# Matrix_Game_Board.net
KiCad netlist of a schematic drawn in EAGLE
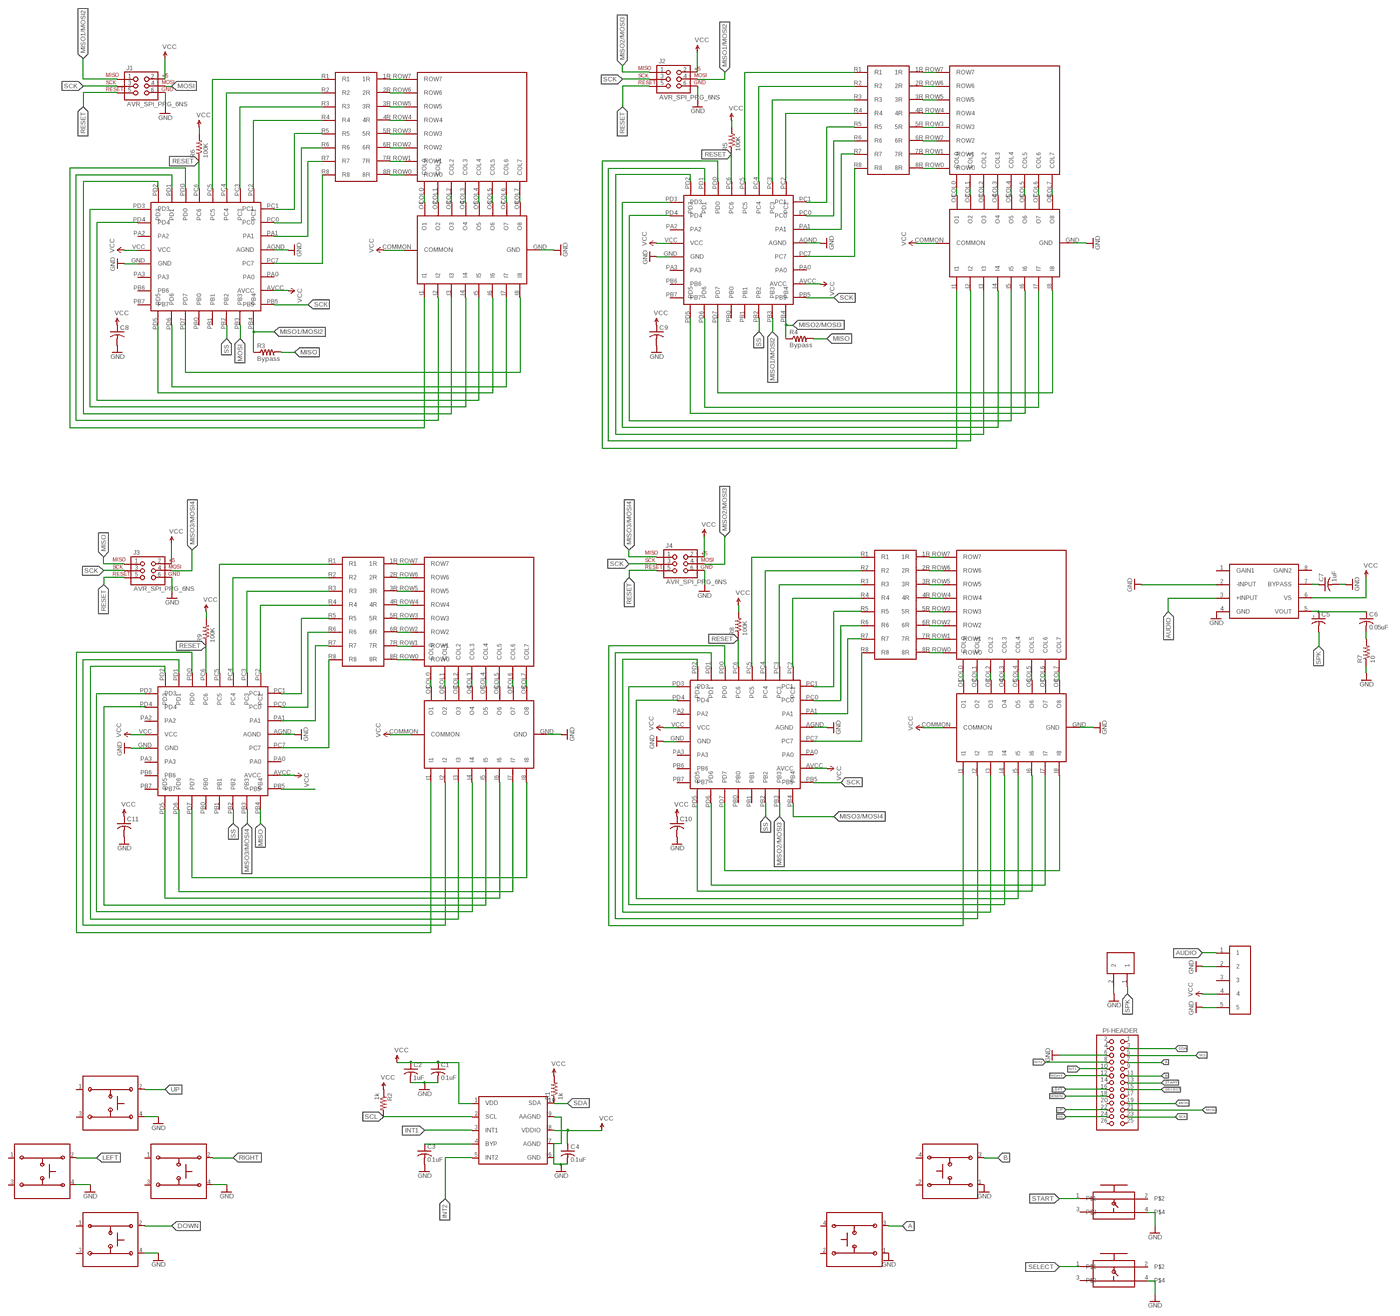
[diagram p0: schematic, sheet 1, overview]
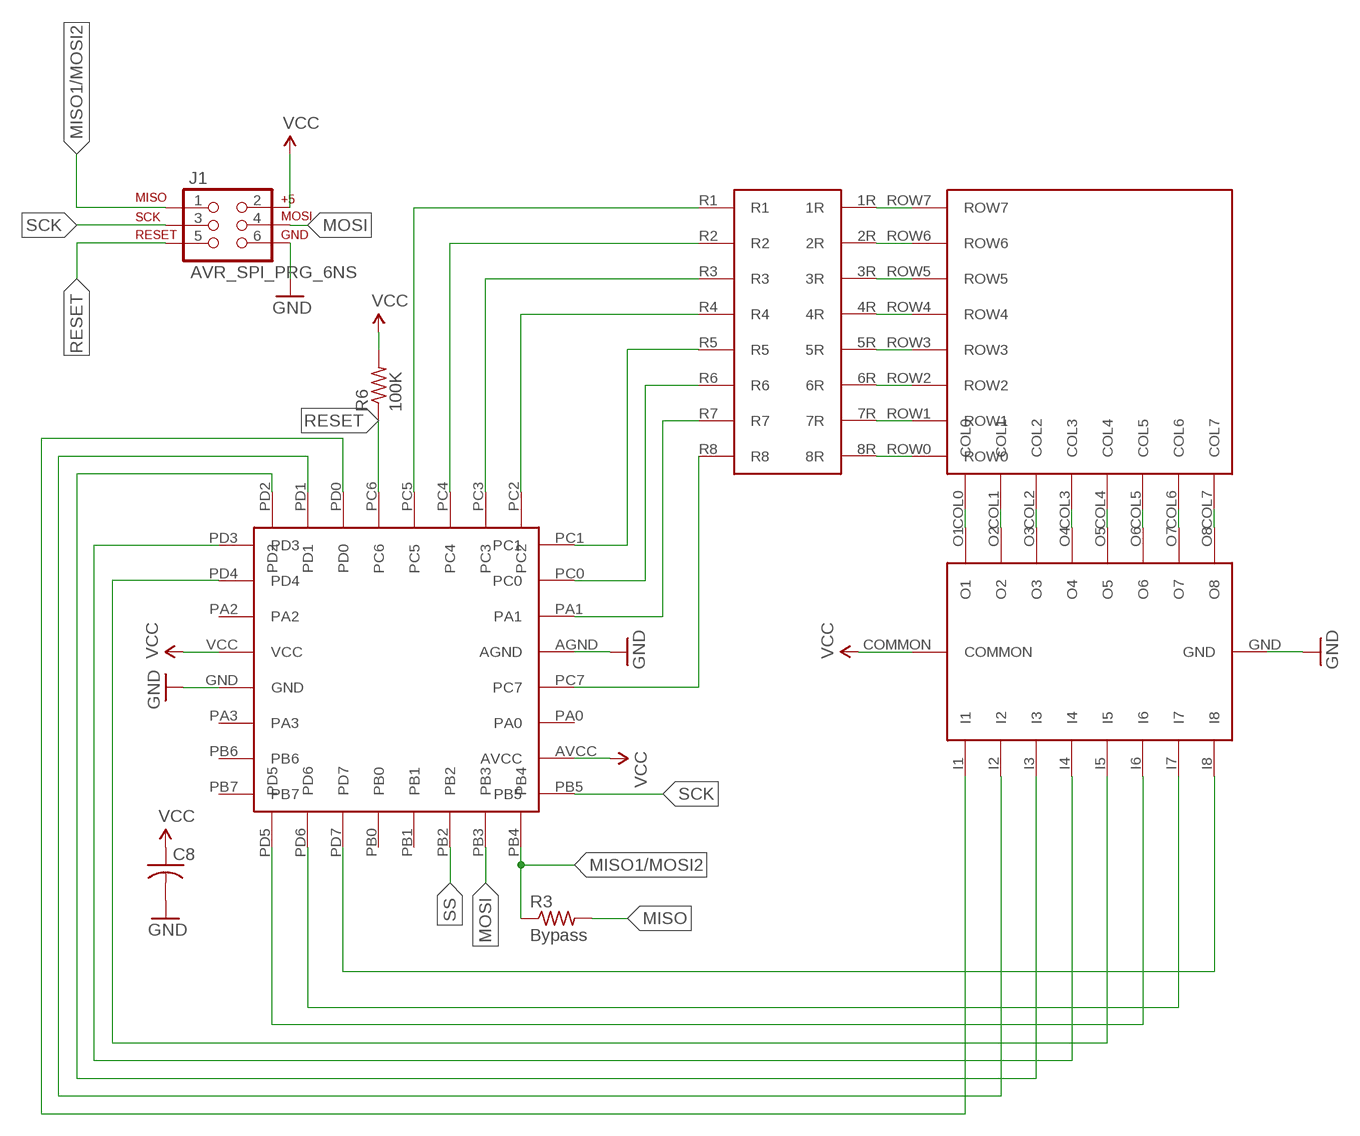
[diagram p1: schematic, sheet 1, part 1 of 4]
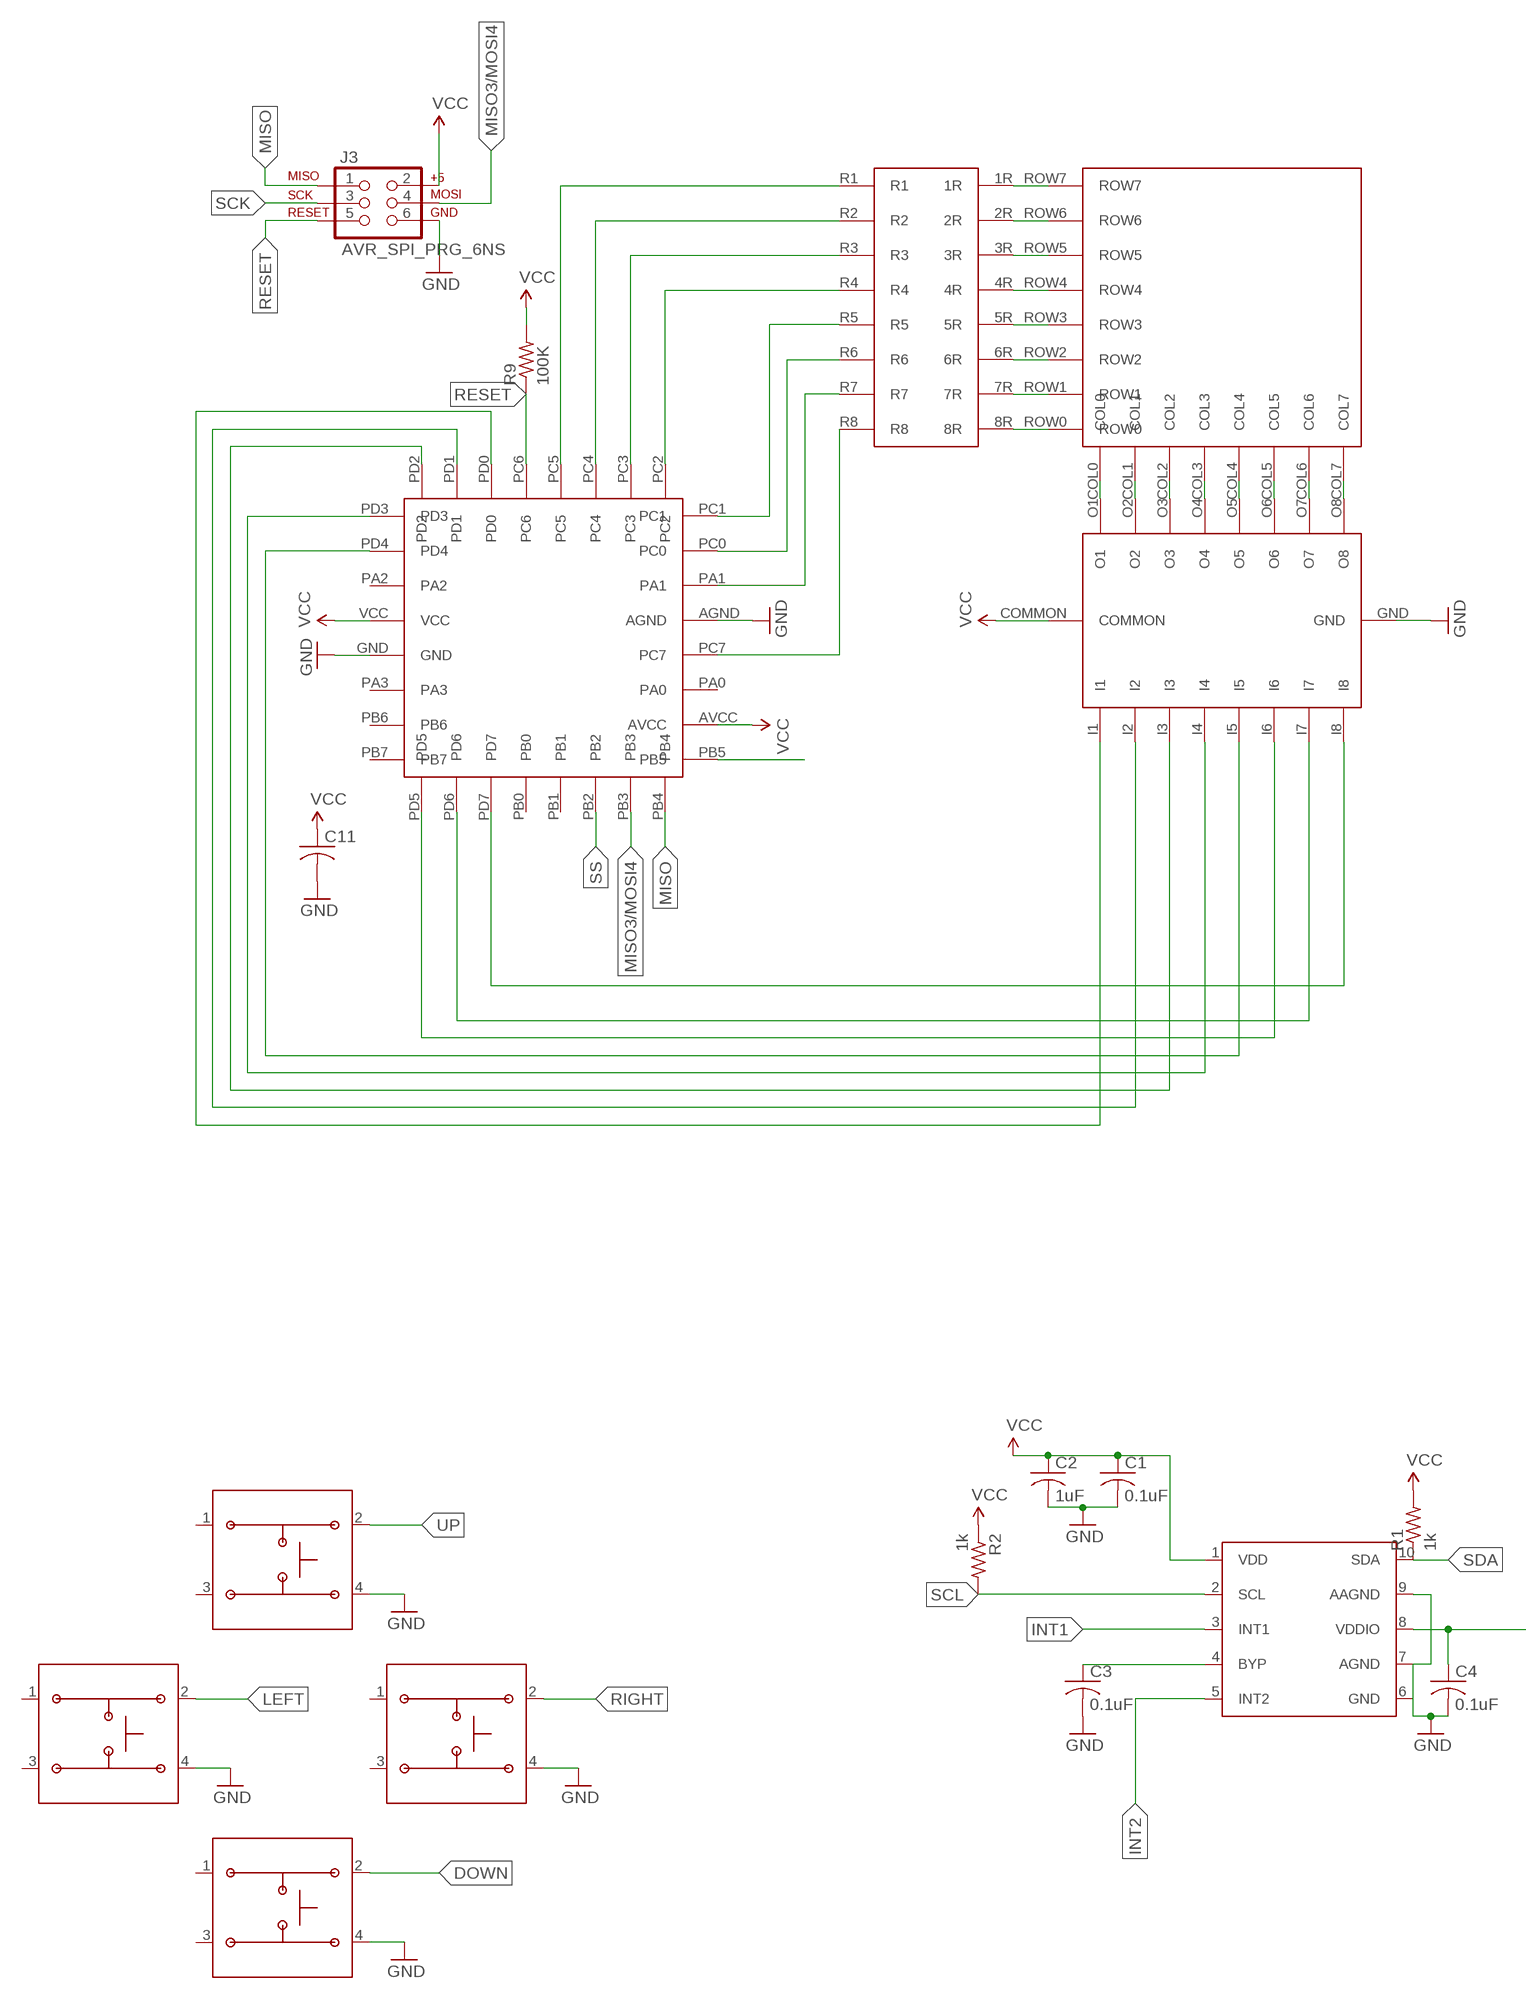
[diagram p2: schematic, sheet 1, part 2 of 4]
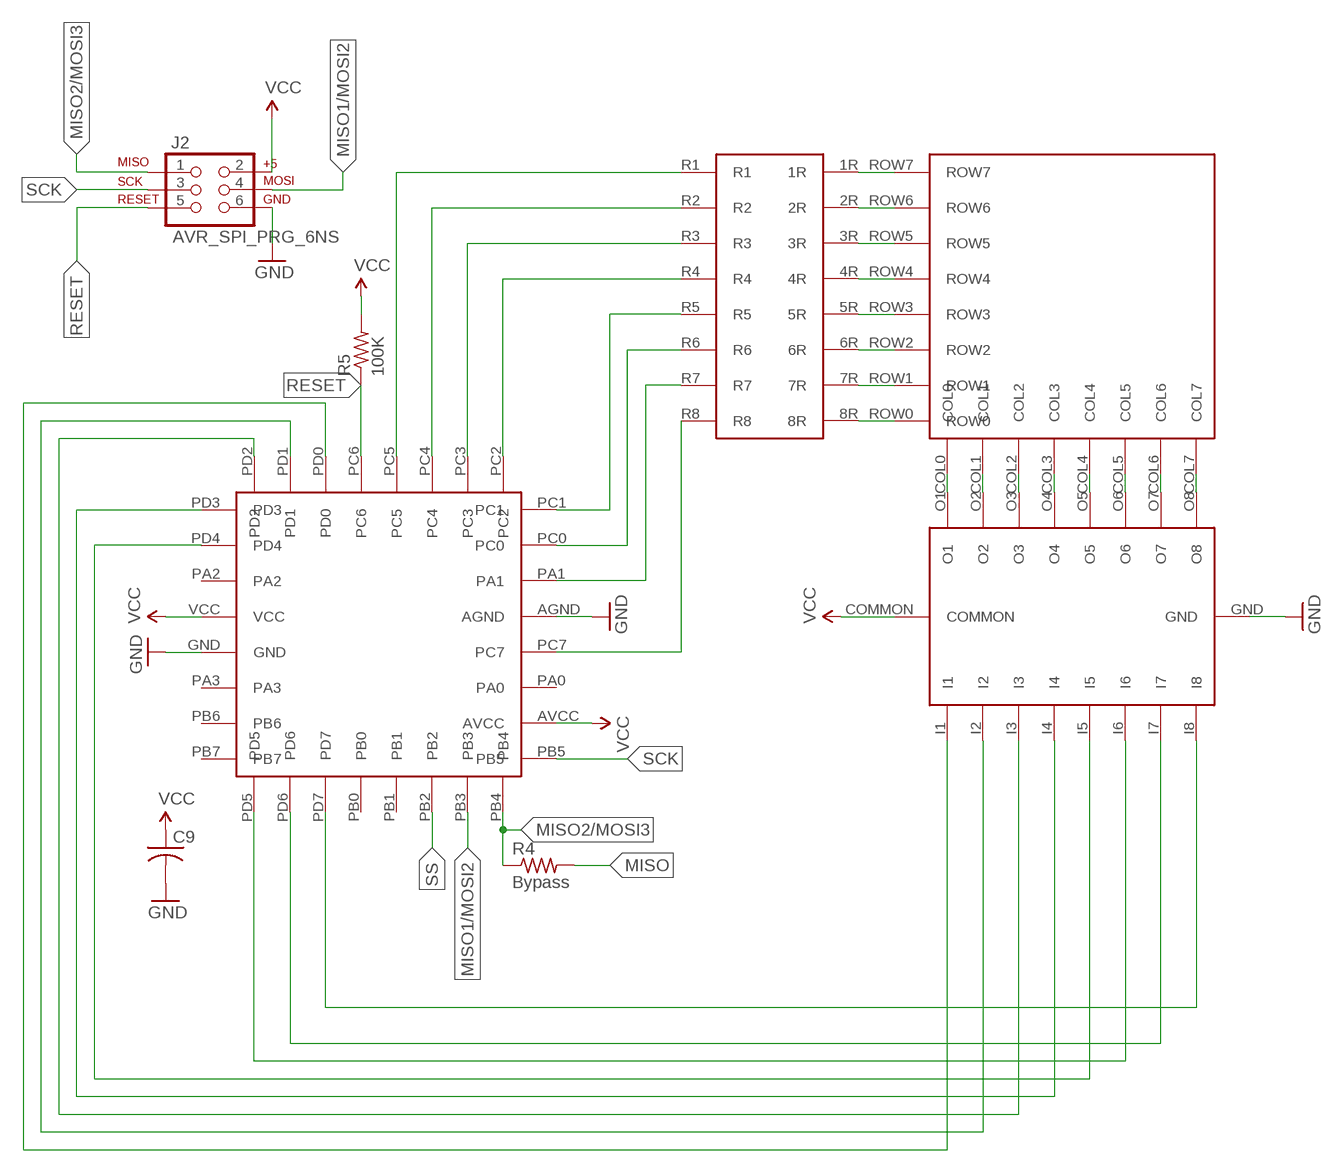
[diagram p3: schematic, sheet 1, part 3 of 4]
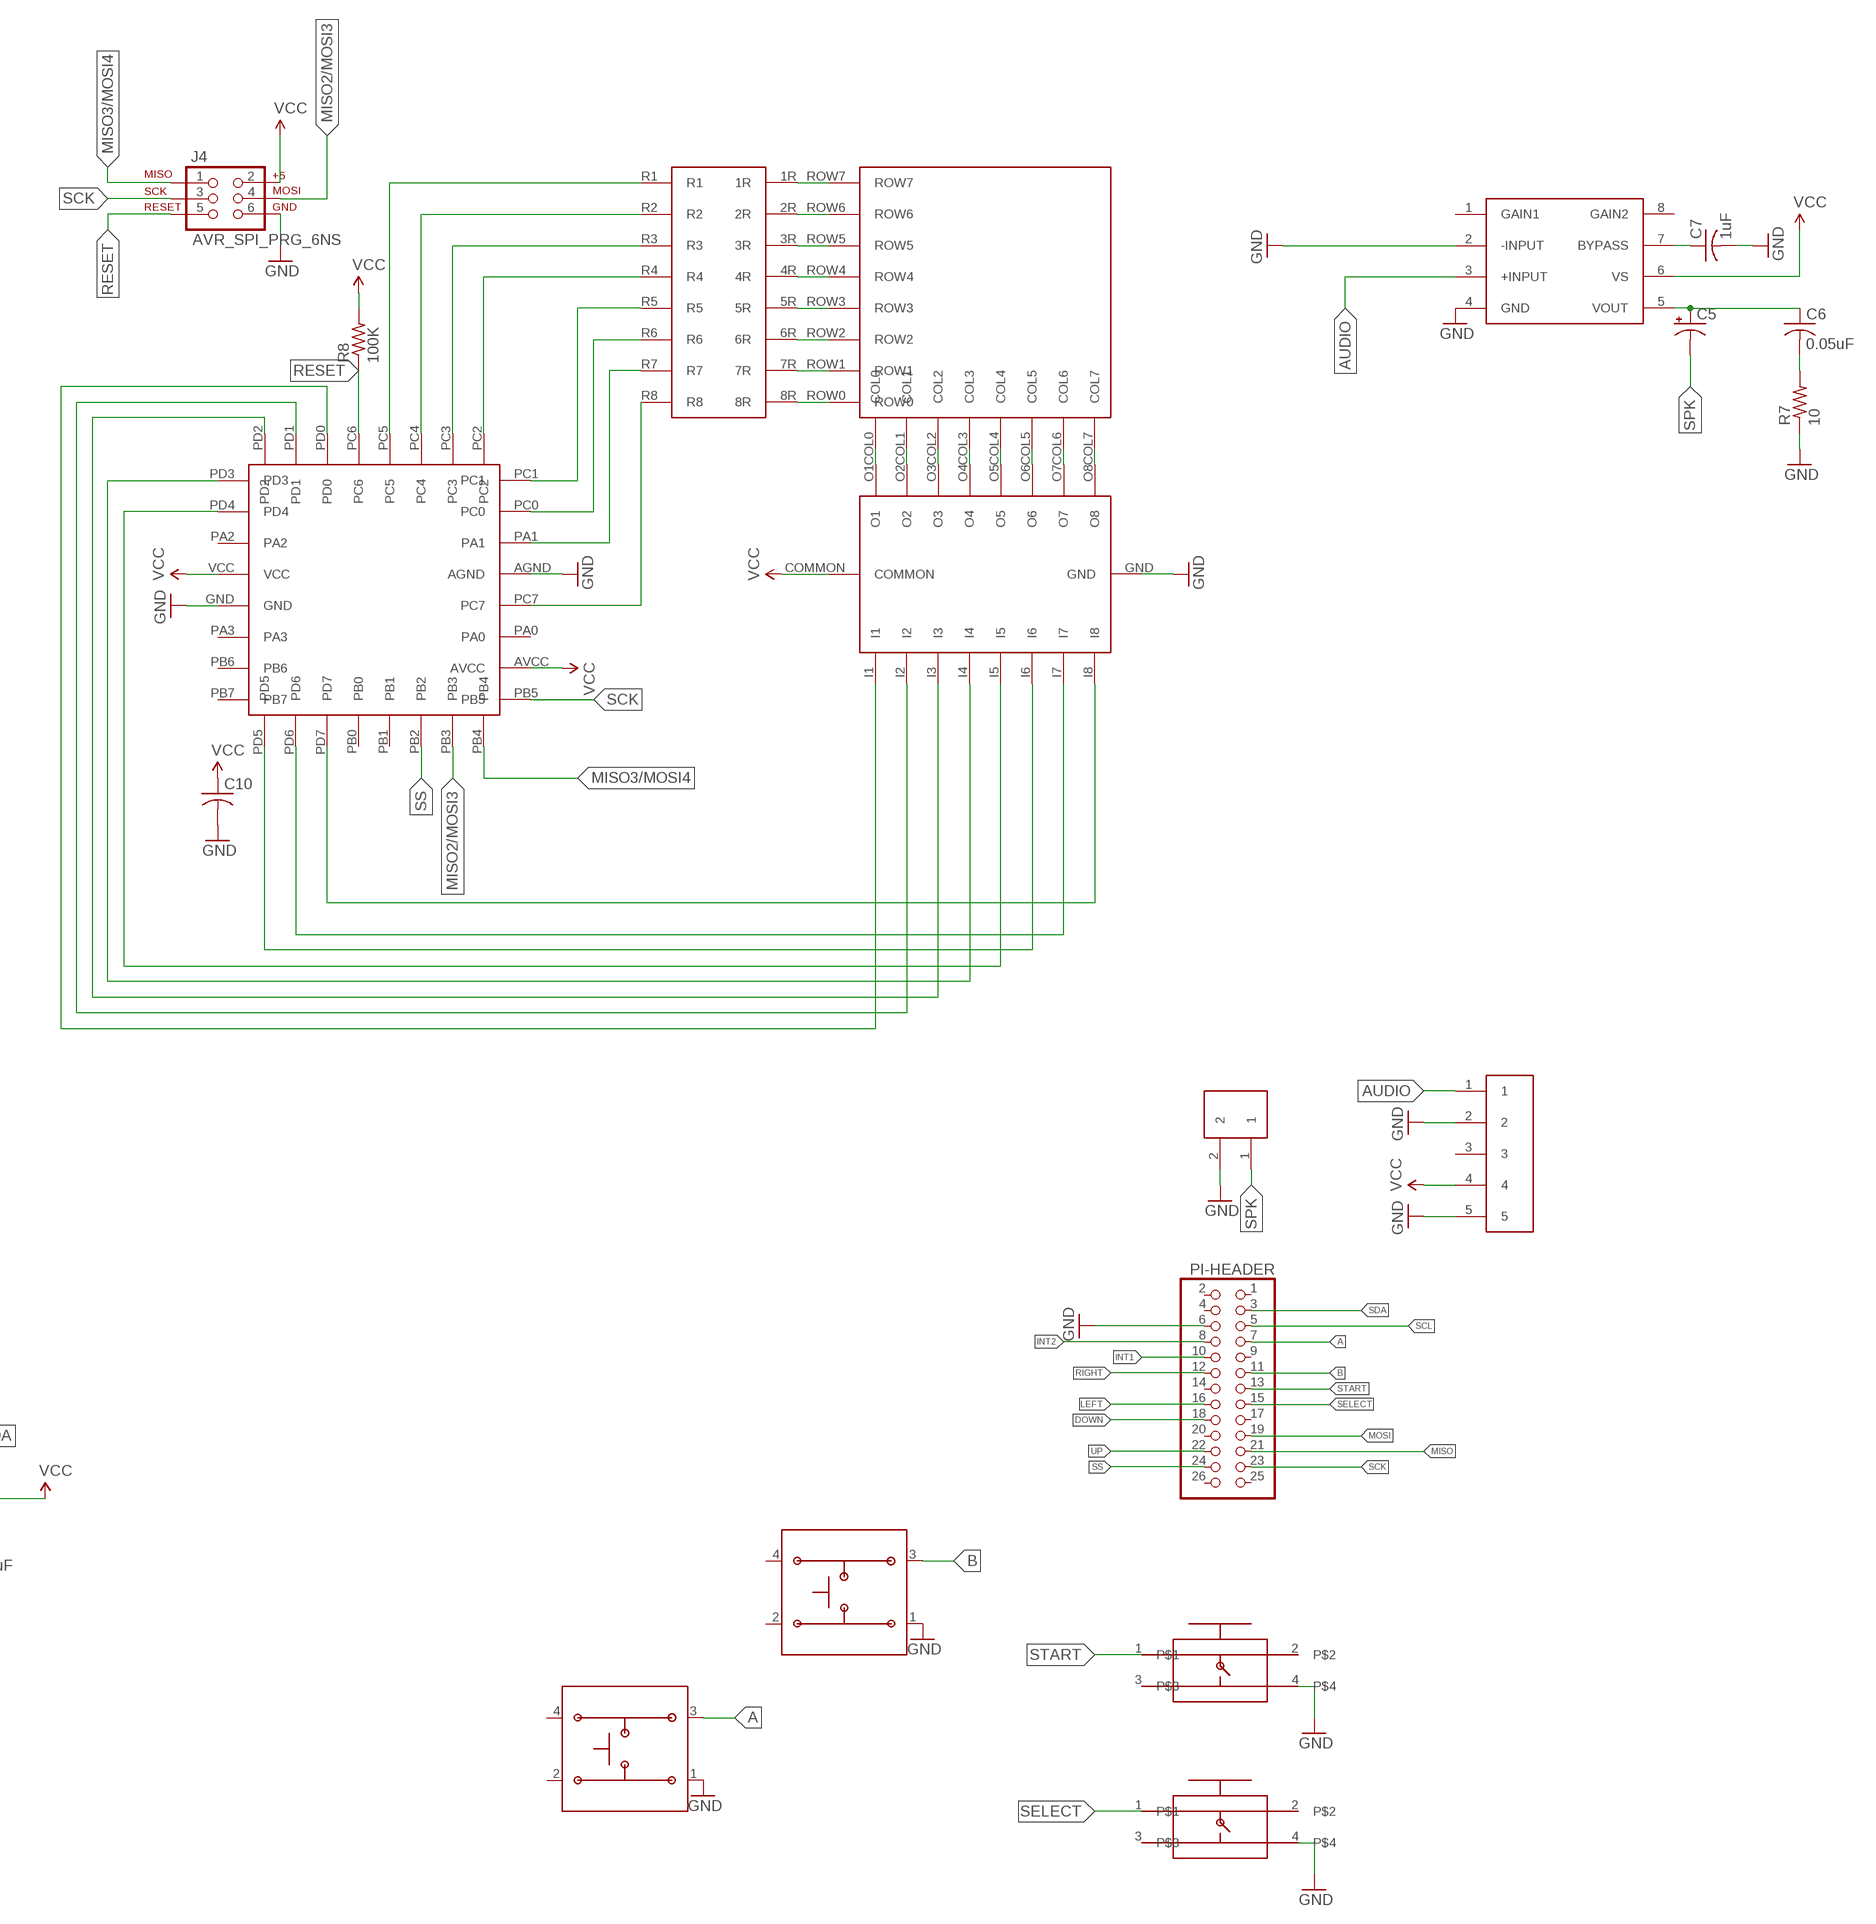
[diagram p4: schematic, sheet 1, part 4 of 4]

(export (version "E")
  (design (tool "Eeschema 10.0.6"))
  (components
    (comp (ref "C1")
      (value "0.1uF")
      (footprint "eagle-import:C0603")
      (libsource (lib "eagle-import") (part "C-USC0603"))
    )
    (comp (ref "C2")
      (value "1uF")
      (footprint "eagle-import:C0603")
      (libsource (lib "eagle-import") (part "C-USC0603"))
    )
    (comp (ref "C3")
      (value "0.1uF")
      (footprint "eagle-import:C0603")
      (libsource (lib "eagle-import") (part "C-USC0603"))
    )
    (comp (ref "C4")
      (value "0.1uF")
      (footprint "eagle-import:C0603")
      (libsource (lib "eagle-import") (part "C-USC0603"))
    )
    (comp (ref "C5")
      (value "CPOL-US153CLV-0605")
      (footprint "eagle-import:153CLV-0605")
      (libsource (lib "eagle-import") (part "CPOL-US153CLV-0605"))
    )
    (comp (ref "C6")
      (value "0.05uF")
      (footprint "eagle-import:C0603")
      (libsource (lib "eagle-import") (part "C-USC0603"))
    )
    (comp (ref "C7")
      (value "1uF")
      (footprint "eagle-import:C0603")
      (libsource (lib "eagle-import") (part "C-USC0603"))
    )
    (comp (ref "C8")
      (value "C-USC0603")
      (footprint "eagle-import:C0603")
      (libsource (lib "eagle-import") (part "C-USC0603"))
    )
    (comp (ref "C9")
      (value "C-USC0603")
      (footprint "eagle-import:C0603")
      (libsource (lib "eagle-import") (part "C-USC0603"))
    )
    (comp (ref "C10")
      (value "C-USC0603")
      (footprint "eagle-import:C0603")
      (libsource (lib "eagle-import") (part "C-USC0603"))
    )
    (comp (ref "C11")
      (value "C-USC0603")
      (footprint "eagle-import:C0603")
      (libsource (lib "eagle-import") (part "C-USC0603"))
    )
    (comp (ref "J1")
      (value "AVR_SPI_PRG_6NS")
      (footprint "eagle-import:2X3-NS")
      (libsource (lib "eagle-import") (part "AVR_SPI_PRG_6NS"))
    )
    (comp (ref "J2")
      (value "AVR_SPI_PRG_6NS")
      (footprint "eagle-import:2X3-NS")
      (libsource (lib "eagle-import") (part "AVR_SPI_PRG_6NS"))
    )
    (comp (ref "J3")
      (value "AVR_SPI_PRG_6NS")
      (footprint "eagle-import:2X3-NS")
      (libsource (lib "eagle-import") (part "AVR_SPI_PRG_6NS"))
    )
    (comp (ref "J4")
      (value "AVR_SPI_PRG_6NS")
      (footprint "eagle-import:2X3-NS")
      (libsource (lib "eagle-import") (part "AVR_SPI_PRG_6NS"))
    )
    (comp (ref "PI-HEADER")
      (value "PINHD-2X13")
      (footprint "eagle-import:2X13")
      (libsource (lib "eagle-import") (part "PINHD-2X13"))
    )
    (comp (ref "R1")
      (value "1k")
      (footprint "eagle-import:R0603")
      (libsource (lib "eagle-import") (part "R-US_R0603"))
    )
    (comp (ref "R2")
      (value "1k")
      (footprint "eagle-import:R0603")
      (libsource (lib "eagle-import") (part "R-US_R0603"))
    )
    (comp (ref "R3")
      (value "Bypass")
      (footprint "eagle-import:R0603")
      (libsource (lib "eagle-import") (part "R-US_R0603"))
    )
    (comp (ref "R4")
      (value "Bypass")
      (footprint "eagle-import:R0603")
      (libsource (lib "eagle-import") (part "R-US_R0603"))
    )
    (comp (ref "R5")
      (value "100K")
      (footprint "eagle-import:R0603")
      (libsource (lib "eagle-import") (part "R-US_R0603"))
    )
    (comp (ref "R6")
      (value "100K")
      (footprint "eagle-import:R0603")
      (libsource (lib "eagle-import") (part "R-US_R0603"))
    )
    (comp (ref "R7")
      (value "10")
      (footprint "eagle-import:R0603")
      (libsource (lib "eagle-import") (part "R-US_R0603"))
    )
    (comp (ref "R8")
      (value "100K")
      (footprint "eagle-import:R0603")
      (libsource (lib "eagle-import") (part "R-US_R0603"))
    )
    (comp (ref "R9")
      (value "100K")
      (footprint "eagle-import:R0603")
      (libsource (lib "eagle-import") (part "R-US_R0603"))
    )
    (comp (ref "U$1")
      (value "8X8_LED_MATRIX")
      (footprint "eagle-import:8X8_LED_MATRIX")
      (libsource (lib "eagle-import") (part "8X8_LED_MATRIX"))
    )
    (comp (ref "U$2")
      (value "RES_ARRAY")
      (footprint "eagle-import:RES_ARRAY")
      (libsource (lib "eagle-import") (part "RES_ARRAY"))
    )
    (comp (ref "U$3")
      (value "8X8_LED_MATRIX")
      (footprint "eagle-import:8X8_LED_MATRIX")
      (libsource (lib "eagle-import") (part "8X8_LED_MATRIX"))
    )
    (comp (ref "U$4")
      (value "ULN2803AFWG")
      (footprint "eagle-import:ULN2803AFWG")
      (libsource (lib "eagle-import") (part "ULN2803AFWG"))
    )
    (comp (ref "U$5")
      (value "ULN2803AFWG")
      (footprint "eagle-import:ULN2803AFWG")
      (libsource (lib "eagle-import") (part "ULN2803AFWG"))
    )
    (comp (ref "U$6")
      (value "ATTINY48")
      (footprint "eagle-import:ATTINY48")
      (libsource (lib "eagle-import") (part "ATTINY48"))
    )
    (comp (ref "U$7")
      (value "RES_ARRAY")
      (footprint "eagle-import:RES_ARRAY")
      (libsource (lib "eagle-import") (part "RES_ARRAY"))
    )
    (comp (ref "U$8")
      (value "8X8_LED_MATRIX")
      (footprint "eagle-import:8X8_LED_MATRIX")
      (libsource (lib "eagle-import") (part "8X8_LED_MATRIX"))
    )
    (comp (ref "U$9")
      (value "ATTINY48")
      (footprint "eagle-import:ATTINY48")
      (libsource (lib "eagle-import") (part "ATTINY48"))
    )
    (comp (ref "U$10")
      (value "ULN2803AFWG")
      (footprint "eagle-import:ULN2803AFWG")
      (libsource (lib "eagle-import") (part "ULN2803AFWG"))
    )
    (comp (ref "U$11")
      (value "ATTINY48")
      (footprint "eagle-import:ATTINY48")
      (libsource (lib "eagle-import") (part "ATTINY48"))
    )
    (comp (ref "U$12")
      (value "RES_ARRAY")
      (footprint "eagle-import:RES_ARRAY")
      (libsource (lib "eagle-import") (part "RES_ARRAY"))
    )
    (comp (ref "U$13")
      (value "8X8_LED_MATRIX")
      (footprint "eagle-import:8X8_LED_MATRIX")
      (libsource (lib "eagle-import") (part "8X8_LED_MATRIX"))
    )
    (comp (ref "U$14")
      (value "ULN2803AFWG")
      (footprint "eagle-import:ULN2803AFWG")
      (libsource (lib "eagle-import") (part "ULN2803AFWG"))
    )
    (comp (ref "U$15")
      (value "ATTINY48")
      (footprint "eagle-import:ATTINY48")
      (libsource (lib "eagle-import") (part "ATTINY48"))
    )
    (comp (ref "U$16")
      (value "RES_ARRAY")
      (footprint "eagle-import:RES_ARRAY")
      (libsource (lib "eagle-import") (part "RES_ARRAY"))
    )
    (comp (ref "U$17")
      (value "12X12MM_BUTTON")
      (footprint "eagle-import:12X12MM_BUTTON")
      (libsource (lib "eagle-import") (part "12X12MM_BUTTON"))
    )
    (comp (ref "U$18")
      (value "12X12MM_BUTTON")
      (footprint "eagle-import:12X12MM_BUTTON")
      (libsource (lib "eagle-import") (part "12X12MM_BUTTON"))
    )
    (comp (ref "U$19")
      (value "12X12MM_BUTTON")
      (footprint "eagle-import:12X12MM_BUTTON")
      (libsource (lib "eagle-import") (part "12X12MM_BUTTON"))
    )
    (comp (ref "U$20")
      (value "12X12MM_BUTTON")
      (footprint "eagle-import:12X12MM_BUTTON")
      (libsource (lib "eagle-import") (part "12X12MM_BUTTON"))
    )
    (comp (ref "U$21")
      (value "12X12MM_BUTTON")
      (footprint "eagle-import:12X12MM_BUTTON")
      (libsource (lib "eagle-import") (part "12X12MM_BUTTON"))
    )
    (comp (ref "U$22")
      (value "12X12MM_BUTTON")
      (footprint "eagle-import:12X12MM_BUTTON")
      (libsource (lib "eagle-import") (part "12X12MM_BUTTON"))
    )
    (comp (ref "U$23")
      (value "MMA8653FCR1")
      (footprint "eagle-import:MMA8653FCR1")
      (libsource (lib "eagle-import") (part "MMA8653FCR1"))
    )
    (comp (ref "U$24")
      (value "SMDTACTILE")
      (footprint "eagle-import:SMDTACTILE")
      (libsource (lib "eagle-import") (part "SMDTACTILE"))
    )
    (comp (ref "U$25")
      (value "LM386")
      (footprint "eagle-import:LM386")
      (libsource (lib "eagle-import") (part "LM386"))
    )
    (comp (ref "U$26")
      (value "SMDTACTILE")
      (footprint "eagle-import:SMDTACTILE")
      (libsource (lib "eagle-import") (part "SMDTACTILE"))
    )
    (comp (ref "U$29")
      (value "DF3_1X2")
      (footprint "eagle-import:DF3_1X2")
      (libsource (lib "eagle-import") (part "DF3_1X2"))
    )
    (comp (ref "U$30")
      (value "DF3_1X5")
      (footprint "eagle-import:DF3_1X5")
      (libsource (lib "eagle-import") (part "DF3_1X5"))
    )
  )
  (nets
    (net (code "1") (name "A") (class "Default")
      (node (ref "PI-HEADER") (pin "7") (pinfunction "7_7") (pintype "passive"))
      (node (ref "U$22") (pin "3") (pinfunction "3_3") (pintype "bidirectional"))
    )
    (net (code "2") (name "AUDIO") (class "Default")
      (node (ref "U$25") (pin "3") (pinfunction "+INPUT_3") (pintype "bidirectional"))
      (node (ref "U$30") (pin "1") (pinfunction "1_1") (pintype "bidirectional"))
    )
    (net (code "3") (name "B") (class "Default")
      (node (ref "PI-HEADER") (pin "11") (pinfunction "11_11") (pintype "passive"))
      (node (ref "U$21") (pin "3") (pinfunction "3_3") (pintype "bidirectional"))
    )
    (net (code "4") (name "DOWN") (class "Default")
      (node (ref "PI-HEADER") (pin "18") (pinfunction "18_18") (pintype "passive"))
      (node (ref "U$20") (pin "2") (pinfunction "2_2") (pintype "bidirectional"))
    )
    (net (code "5") (name "GND") (class "Default")
      (node (ref "C1") (pin "2") (pinfunction "2_2") (pintype "passive"))
      (node (ref "C10") (pin "2") (pinfunction "2_2") (pintype "passive"))
      (node (ref "C11") (pin "2") (pinfunction "2_2") (pintype "passive"))
      (node (ref "C2") (pin "2") (pinfunction "2_2") (pintype "passive"))
      (node (ref "C3") (pin "2") (pinfunction "2_2") (pintype "passive"))
      (node (ref "C4") (pin "2") (pinfunction "2_2") (pintype "passive"))
      (node (ref "C7") (pin "2") (pinfunction "2_2") (pintype "passive"))
      (node (ref "C8") (pin "2") (pinfunction "2_2") (pintype "passive"))
      (node (ref "C9") (pin "2") (pinfunction "2_2") (pintype "passive"))
      (node (ref "J1") (pin "6") (pinfunction "6_6") (pintype "passive"))
      (node (ref "J2") (pin "6") (pinfunction "6_6") (pintype "passive"))
      (node (ref "J3") (pin "6") (pinfunction "6_6") (pintype "passive"))
      (node (ref "J4") (pin "6") (pinfunction "6_6") (pintype "passive"))
      (node (ref "PI-HEADER") (pin "6") (pinfunction "6_6") (pintype "passive"))
      (node (ref "R7") (pin "1") (pinfunction "1_1") (pintype "passive"))
      (node (ref "U$10") (pin "GND") (pinfunction "GND_GND") (pintype "bidirectional"))
      (node (ref "U$11") (pin "AGND") (pinfunction "AGND_AGND") (pintype "bidirectional"))
      (node (ref "U$11") (pin "GND") (pinfunction "GND_GND") (pintype "bidirectional"))
      (node (ref "U$14") (pin "GND") (pinfunction "GND_GND") (pintype "bidirectional"))
      (node (ref "U$15") (pin "AGND") (pinfunction "AGND_AGND") (pintype "bidirectional"))
      (node (ref "U$15") (pin "GND") (pinfunction "GND_GND") (pintype "bidirectional"))
      (node (ref "U$17") (pin "4") (pinfunction "4_4") (pintype "bidirectional"))
      (node (ref "U$18") (pin "4") (pinfunction "4_4") (pintype "bidirectional"))
      (node (ref "U$19") (pin "4") (pinfunction "4_4") (pintype "bidirectional"))
      (node (ref "U$20") (pin "4") (pinfunction "4_4") (pintype "bidirectional"))
      (node (ref "U$21") (pin "1") (pinfunction "1_1") (pintype "bidirectional"))
      (node (ref "U$22") (pin "1") (pinfunction "1_1") (pintype "bidirectional"))
      (node (ref "U$23") (pin "6") (pinfunction "GND_6") (pintype "bidirectional"))
      (node (ref "U$23") (pin "7") (pinfunction "AGND_7") (pintype "bidirectional"))
      (node (ref "U$23") (pin "9") (pinfunction "AAGND_9") (pintype "bidirectional"))
      (node (ref "U$24") (pin "4") (pinfunction "P$4_4") (pintype "bidirectional"))
      (node (ref "U$25") (pin "2") (pinfunction "-INPUT_2") (pintype "bidirectional"))
      (node (ref "U$25") (pin "4") (pinfunction "GND_4") (pintype "bidirectional"))
      (node (ref "U$26") (pin "4") (pinfunction "P$4_4") (pintype "bidirectional"))
      (node (ref "U$29") (pin "2") (pinfunction "2_2") (pintype "bidirectional"))
      (node (ref "U$30") (pin "2") (pinfunction "2_2") (pintype "bidirectional"))
      (node (ref "U$30") (pin "5") (pinfunction "5_5") (pintype "bidirectional"))
      (node (ref "U$4") (pin "GND") (pinfunction "GND_GND") (pintype "bidirectional"))
      (node (ref "U$5") (pin "GND") (pinfunction "GND_GND") (pintype "bidirectional"))
      (node (ref "U$6") (pin "AGND") (pinfunction "AGND_AGND") (pintype "bidirectional"))
      (node (ref "U$6") (pin "GND") (pinfunction "GND_GND") (pintype "bidirectional"))
      (node (ref "U$9") (pin "AGND") (pinfunction "AGND_AGND") (pintype "bidirectional"))
      (node (ref "U$9") (pin "GND") (pinfunction "GND_GND") (pintype "bidirectional"))
    )
    (net (code "6") (name "INT1") (class "Default")
      (node (ref "PI-HEADER") (pin "10") (pinfunction "10_10") (pintype "passive"))
      (node (ref "U$23") (pin "3") (pinfunction "INT1_3") (pintype "bidirectional"))
    )
    (net (code "7") (name "INT2") (class "Default")
      (node (ref "PI-HEADER") (pin "8") (pinfunction "8_8") (pintype "passive"))
      (node (ref "U$23") (pin "5") (pinfunction "INT2_5") (pintype "bidirectional"))
    )
    (net (code "8") (name "LEFT") (class "Default")
      (node (ref "PI-HEADER") (pin "16") (pinfunction "16_16") (pintype "passive"))
      (node (ref "U$18") (pin "2") (pinfunction "2_2") (pintype "bidirectional"))
    )
    (net (code "9") (name "MISO") (class "Default")
      (node (ref "J3") (pin "1") (pinfunction "1_1") (pintype "passive"))
      (node (ref "PI-HEADER") (pin "21") (pinfunction "21_21") (pintype "passive"))
      (node (ref "R3") (pin "2") (pinfunction "2_2") (pintype "passive"))
      (node (ref "R4") (pin "2") (pinfunction "2_2") (pintype "passive"))
      (node (ref "U$11") (pin "PB4") (pinfunction "PB4_PB4") (pintype "bidirectional"))
    )
    (net (code "10") (name "MISO1{slash}MOSI2") (class "Default")
      (node (ref "J1") (pin "1") (pinfunction "1_1") (pintype "passive"))
      (node (ref "J2") (pin "4") (pinfunction "4_4") (pintype "passive"))
      (node (ref "R3") (pin "1") (pinfunction "1_1") (pintype "passive"))
      (node (ref "U$6") (pin "PB3") (pinfunction "PB3_PB3") (pintype "bidirectional"))
      (node (ref "U$9") (pin "PB4") (pinfunction "PB4_PB4") (pintype "bidirectional"))
    )
    (net (code "11") (name "MISO2{slash}MOSI3") (class "Default")
      (node (ref "J2") (pin "1") (pinfunction "1_1") (pintype "passive"))
      (node (ref "J4") (pin "4") (pinfunction "4_4") (pintype "passive"))
      (node (ref "R4") (pin "1") (pinfunction "1_1") (pintype "passive"))
      (node (ref "U$15") (pin "PB3") (pinfunction "PB3_PB3") (pintype "bidirectional"))
      (node (ref "U$6") (pin "PB4") (pinfunction "PB4_PB4") (pintype "bidirectional"))
    )
    (net (code "12") (name "MISO3{slash}MOSI4") (class "Default")
      (node (ref "J3") (pin "4") (pinfunction "4_4") (pintype "passive"))
      (node (ref "J4") (pin "1") (pinfunction "1_1") (pintype "passive"))
      (node (ref "U$11") (pin "PB3") (pinfunction "PB3_PB3") (pintype "bidirectional"))
      (node (ref "U$15") (pin "PB4") (pinfunction "PB4_PB4") (pintype "bidirectional"))
    )
    (net (code "13") (name "MOSI") (class "Default")
      (node (ref "J1") (pin "4") (pinfunction "4_4") (pintype "passive"))
      (node (ref "PI-HEADER") (pin "19") (pinfunction "19_19") (pintype "passive"))
      (node (ref "U$9") (pin "PB3") (pinfunction "PB3_PB3") (pintype "bidirectional"))
    )
    (net (code "14") (name "Net-(C6-Pad2)") (class "Default")
      (node (ref "C6") (pin "2") (pinfunction "2_2") (pintype "passive"))
      (node (ref "R7") (pin "2") (pinfunction "2_2") (pintype "passive"))
    )
    (net (code "15") (name "Net-(U$1-PadCOL0)") (class "Default")
      (node (ref "U$1") (pin "COL0") (pinfunction "COL0_COL0") (pintype "bidirectional"))
      (node (ref "U$5") (pin "O1") (pinfunction "O1_O1") (pintype "bidirectional"))
    )
    (net (code "16") (name "Net-(U$1-PadCOL1)") (class "Default")
      (node (ref "U$1") (pin "COL1") (pinfunction "COL1_COL1") (pintype "bidirectional"))
      (node (ref "U$5") (pin "O2") (pinfunction "O2_O2") (pintype "bidirectional"))
    )
    (net (code "17") (name "Net-(U$1-PadCOL2)") (class "Default")
      (node (ref "U$1") (pin "COL2") (pinfunction "COL2_COL2") (pintype "bidirectional"))
      (node (ref "U$5") (pin "O3") (pinfunction "O3_O3") (pintype "bidirectional"))
    )
    (net (code "18") (name "Net-(U$1-PadCOL3)") (class "Default")
      (node (ref "U$1") (pin "COL3") (pinfunction "COL3_COL3") (pintype "bidirectional"))
      (node (ref "U$5") (pin "O4") (pinfunction "O4_O4") (pintype "bidirectional"))
    )
    (net (code "19") (name "Net-(U$1-PadCOL4)") (class "Default")
      (node (ref "U$1") (pin "COL4") (pinfunction "COL4_COL4") (pintype "bidirectional"))
      (node (ref "U$5") (pin "O5") (pinfunction "O5_O5") (pintype "bidirectional"))
    )
    (net (code "20") (name "Net-(U$1-PadCOL5)") (class "Default")
      (node (ref "U$1") (pin "COL5") (pinfunction "COL5_COL5") (pintype "bidirectional"))
      (node (ref "U$5") (pin "O6") (pinfunction "O6_O6") (pintype "bidirectional"))
    )
    (net (code "21") (name "Net-(U$1-PadCOL6)") (class "Default")
      (node (ref "U$1") (pin "COL6") (pinfunction "COL6_COL6") (pintype "bidirectional"))
      (node (ref "U$5") (pin "O7") (pinfunction "O7_O7") (pintype "bidirectional"))
    )
    (net (code "22") (name "Net-(U$1-PadCOL7)") (class "Default")
      (node (ref "U$1") (pin "COL7") (pinfunction "COL7_COL7") (pintype "bidirectional"))
      (node (ref "U$5") (pin "O8") (pinfunction "O8_O8") (pintype "bidirectional"))
    )
    (net (code "23") (name "Net-(U$1-PadROW0)") (class "Default")
      (node (ref "U$1") (pin "ROW0") (pinfunction "ROW0_ROW0") (pintype "bidirectional"))
      (node (ref "U$2") (pin "8R") (pinfunction "8R_8R") (pintype "bidirectional"))
    )
    (net (code "24") (name "Net-(U$1-PadROW1)") (class "Default")
      (node (ref "U$1") (pin "ROW1") (pinfunction "ROW1_ROW1") (pintype "bidirectional"))
      (node (ref "U$2") (pin "7R") (pinfunction "7R_7R") (pintype "bidirectional"))
    )
    (net (code "25") (name "Net-(U$1-PadROW2)") (class "Default")
      (node (ref "U$1") (pin "ROW2") (pinfunction "ROW2_ROW2") (pintype "bidirectional"))
      (node (ref "U$2") (pin "6R") (pinfunction "6R_6R") (pintype "bidirectional"))
    )
    (net (code "26") (name "Net-(U$1-PadROW3)") (class "Default")
      (node (ref "U$1") (pin "ROW3") (pinfunction "ROW3_ROW3") (pintype "bidirectional"))
      (node (ref "U$2") (pin "5R") (pinfunction "5R_5R") (pintype "bidirectional"))
    )
    (net (code "27") (name "Net-(U$1-PadROW4)") (class "Default")
      (node (ref "U$1") (pin "ROW4") (pinfunction "ROW4_ROW4") (pintype "bidirectional"))
      (node (ref "U$2") (pin "4R") (pinfunction "4R_4R") (pintype "bidirectional"))
    )
    (net (code "28") (name "Net-(U$1-PadROW5)") (class "Default")
      (node (ref "U$1") (pin "ROW5") (pinfunction "ROW5_ROW5") (pintype "bidirectional"))
      (node (ref "U$2") (pin "3R") (pinfunction "3R_3R") (pintype "bidirectional"))
    )
    (net (code "29") (name "Net-(U$1-PadROW6)") (class "Default")
      (node (ref "U$1") (pin "ROW6") (pinfunction "ROW6_ROW6") (pintype "bidirectional"))
      (node (ref "U$2") (pin "2R") (pinfunction "2R_2R") (pintype "bidirectional"))
    )
    (net (code "30") (name "Net-(U$1-PadROW7)") (class "Default")
      (node (ref "U$1") (pin "ROW7") (pinfunction "ROW7_ROW7") (pintype "bidirectional"))
      (node (ref "U$2") (pin "1R") (pinfunction "1R_1R") (pintype "bidirectional"))
    )
    (net (code "31") (name "Net-(U$2-PadR1)") (class "Default")
      (node (ref "U$2") (pin "R1") (pinfunction "R1_R1") (pintype "bidirectional"))
      (node (ref "U$9") (pin "PC5") (pinfunction "PC5_PC5") (pintype "bidirectional"))
    )
    (net (code "32") (name "Net-(U$2-PadR2)") (class "Default")
      (node (ref "U$2") (pin "R2") (pinfunction "R2_R2") (pintype "bidirectional"))
      (node (ref "U$9") (pin "PC4") (pinfunction "PC4_PC4") (pintype "bidirectional"))
    )
    (net (code "33") (name "Net-(U$2-PadR3)") (class "Default")
      (node (ref "U$2") (pin "R3") (pinfunction "R3_R3") (pintype "bidirectional"))
      (node (ref "U$9") (pin "PC3") (pinfunction "PC3_PC3") (pintype "bidirectional"))
    )
    (net (code "34") (name "Net-(U$2-PadR4)") (class "Default")
      (node (ref "U$2") (pin "R4") (pinfunction "R4_R4") (pintype "bidirectional"))
      (node (ref "U$9") (pin "PC2") (pinfunction "PC2_PC2") (pintype "bidirectional"))
    )
    (net (code "35") (name "Net-(U$2-PadR5)") (class "Default")
      (node (ref "U$2") (pin "R5") (pinfunction "R5_R5") (pintype "bidirectional"))
      (node (ref "U$9") (pin "PC1") (pinfunction "PC1_PC1") (pintype "bidirectional"))
    )
    (net (code "36") (name "Net-(U$2-PadR6)") (class "Default")
      (node (ref "U$2") (pin "R6") (pinfunction "R6_R6") (pintype "bidirectional"))
      (node (ref "U$9") (pin "PC0") (pinfunction "PC0_PC0") (pintype "bidirectional"))
    )
    (net (code "37") (name "Net-(U$2-PadR7)") (class "Default")
      (node (ref "U$2") (pin "R7") (pinfunction "R7_R7") (pintype "bidirectional"))
      (node (ref "U$9") (pin "PA1") (pinfunction "PA1_PA1") (pintype "bidirectional"))
    )
    (net (code "38") (name "Net-(U$2-PadR8)") (class "Default")
      (node (ref "U$2") (pin "R8") (pinfunction "R8_R8") (pintype "bidirectional"))
      (node (ref "U$9") (pin "PC7") (pinfunction "PC7_PC7") (pintype "bidirectional"))
    )
    (net (code "39") (name "Net-(U$3-PadCOL0)") (class "Default")
      (node (ref "U$3") (pin "COL0") (pinfunction "COL0_COL0") (pintype "bidirectional"))
      (node (ref "U$4") (pin "O1") (pinfunction "O1_O1") (pintype "bidirectional"))
    )
    (net (code "40") (name "Net-(U$3-PadCOL1)") (class "Default")
      (node (ref "U$3") (pin "COL1") (pinfunction "COL1_COL1") (pintype "bidirectional"))
      (node (ref "U$4") (pin "O2") (pinfunction "O2_O2") (pintype "bidirectional"))
    )
    (net (code "41") (name "Net-(U$3-PadCOL2)") (class "Default")
      (node (ref "U$3") (pin "COL2") (pinfunction "COL2_COL2") (pintype "bidirectional"))
      (node (ref "U$4") (pin "O3") (pinfunction "O3_O3") (pintype "bidirectional"))
    )
    (net (code "42") (name "Net-(U$3-PadCOL3)") (class "Default")
      (node (ref "U$3") (pin "COL3") (pinfunction "COL3_COL3") (pintype "bidirectional"))
      (node (ref "U$4") (pin "O4") (pinfunction "O4_O4") (pintype "bidirectional"))
    )
    (net (code "43") (name "Net-(U$3-PadCOL4)") (class "Default")
      (node (ref "U$3") (pin "COL4") (pinfunction "COL4_COL4") (pintype "bidirectional"))
      (node (ref "U$4") (pin "O5") (pinfunction "O5_O5") (pintype "bidirectional"))
    )
    (net (code "44") (name "Net-(U$3-PadCOL5)") (class "Default")
      (node (ref "U$3") (pin "COL5") (pinfunction "COL5_COL5") (pintype "bidirectional"))
      (node (ref "U$4") (pin "O6") (pinfunction "O6_O6") (pintype "bidirectional"))
    )
    (net (code "45") (name "Net-(U$3-PadCOL6)") (class "Default")
      (node (ref "U$3") (pin "COL6") (pinfunction "COL6_COL6") (pintype "bidirectional"))
      (node (ref "U$4") (pin "O7") (pinfunction "O7_O7") (pintype "bidirectional"))
    )
    (net (code "46") (name "Net-(U$3-PadCOL7)") (class "Default")
      (node (ref "U$3") (pin "COL7") (pinfunction "COL7_COL7") (pintype "bidirectional"))
      (node (ref "U$4") (pin "O8") (pinfunction "O8_O8") (pintype "bidirectional"))
    )
    (net (code "47") (name "Net-(U$3-PadROW0)") (class "Default")
      (node (ref "U$3") (pin "ROW0") (pinfunction "ROW0_ROW0") (pintype "bidirectional"))
      (node (ref "U$7") (pin "8R") (pinfunction "8R_8R") (pintype "bidirectional"))
    )
    (net (code "48") (name "Net-(U$3-PadROW1)") (class "Default")
      (node (ref "U$3") (pin "ROW1") (pinfunction "ROW1_ROW1") (pintype "bidirectional"))
      (node (ref "U$7") (pin "7R") (pinfunction "7R_7R") (pintype "bidirectional"))
    )
    (net (code "49") (name "Net-(U$3-PadROW2)") (class "Default")
      (node (ref "U$3") (pin "ROW2") (pinfunction "ROW2_ROW2") (pintype "bidirectional"))
      (node (ref "U$7") (pin "6R") (pinfunction "6R_6R") (pintype "bidirectional"))
    )
    (net (code "50") (name "Net-(U$3-PadROW3)") (class "Default")
      (node (ref "U$3") (pin "ROW3") (pinfunction "ROW3_ROW3") (pintype "bidirectional"))
      (node (ref "U$7") (pin "5R") (pinfunction "5R_5R") (pintype "bidirectional"))
    )
    (net (code "51") (name "Net-(U$3-PadROW4)") (class "Default")
      (node (ref "U$3") (pin "ROW4") (pinfunction "ROW4_ROW4") (pintype "bidirectional"))
      (node (ref "U$7") (pin "4R") (pinfunction "4R_4R") (pintype "bidirectional"))
    )
    (net (code "52") (name "Net-(U$3-PadROW5)") (class "Default")
      (node (ref "U$3") (pin "ROW5") (pinfunction "ROW5_ROW5") (pintype "bidirectional"))
      (node (ref "U$7") (pin "3R") (pinfunction "3R_3R") (pintype "bidirectional"))
    )
    (net (code "53") (name "Net-(U$3-PadROW6)") (class "Default")
      (node (ref "U$3") (pin "ROW6") (pinfunction "ROW6_ROW6") (pintype "bidirectional"))
      (node (ref "U$7") (pin "2R") (pinfunction "2R_2R") (pintype "bidirectional"))
    )
    (net (code "54") (name "Net-(U$3-PadROW7)") (class "Default")
      (node (ref "U$3") (pin "ROW7") (pinfunction "ROW7_ROW7") (pintype "bidirectional"))
      (node (ref "U$7") (pin "1R") (pinfunction "1R_1R") (pintype "bidirectional"))
    )
    (net (code "55") (name "Net-(U$4-PadI1)") (class "Default")
      (node (ref "U$4") (pin "I1") (pinfunction "I1_I1") (pintype "bidirectional"))
      (node (ref "U$6") (pin "PD0") (pinfunction "PD0_PD0") (pintype "bidirectional"))
    )
    (net (code "56") (name "Net-(U$4-PadI2)") (class "Default")
      (node (ref "U$4") (pin "I2") (pinfunction "I2_I2") (pintype "bidirectional"))
      (node (ref "U$6") (pin "PD1") (pinfunction "PD1_PD1") (pintype "bidirectional"))
    )
    (net (code "57") (name "Net-(U$4-PadI3)") (class "Default")
      (node (ref "U$4") (pin "I3") (pinfunction "I3_I3") (pintype "bidirectional"))
      (node (ref "U$6") (pin "PD2") (pinfunction "PD2_PD2") (pintype "bidirectional"))
    )
    (net (code "58") (name "Net-(U$4-PadI4)") (class "Default")
      (node (ref "U$4") (pin "I4") (pinfunction "I4_I4") (pintype "bidirectional"))
      (node (ref "U$6") (pin "PD3") (pinfunction "PD3_PD3") (pintype "bidirectional"))
    )
    (net (code "59") (name "Net-(U$4-PadI5)") (class "Default")
      (node (ref "U$4") (pin "I5") (pinfunction "I5_I5") (pintype "bidirectional"))
      (node (ref "U$6") (pin "PD4") (pinfunction "PD4_PD4") (pintype "bidirectional"))
    )
    (net (code "60") (name "Net-(U$4-PadI6)") (class "Default")
      (node (ref "U$4") (pin "I6") (pinfunction "I6_I6") (pintype "bidirectional"))
      (node (ref "U$6") (pin "PD5") (pinfunction "PD5_PD5") (pintype "bidirectional"))
    )
    (net (code "61") (name "Net-(U$4-PadI7)") (class "Default")
      (node (ref "U$4") (pin "I7") (pinfunction "I7_I7") (pintype "bidirectional"))
      (node (ref "U$6") (pin "PD6") (pinfunction "PD6_PD6") (pintype "bidirectional"))
    )
    (net (code "62") (name "Net-(U$4-PadI8)") (class "Default")
      (node (ref "U$4") (pin "I8") (pinfunction "I8_I8") (pintype "bidirectional"))
      (node (ref "U$6") (pin "PD7") (pinfunction "PD7_PD7") (pintype "bidirectional"))
    )
    (net (code "63") (name "Net-(U$5-PadI1)") (class "Default")
      (node (ref "U$5") (pin "I1") (pinfunction "I1_I1") (pintype "bidirectional"))
      (node (ref "U$9") (pin "PD0") (pinfunction "PD0_PD0") (pintype "bidirectional"))
    )
    (net (code "64") (name "Net-(U$5-PadI2)") (class "Default")
      (node (ref "U$5") (pin "I2") (pinfunction "I2_I2") (pintype "bidirectional"))
      (node (ref "U$9") (pin "PD1") (pinfunction "PD1_PD1") (pintype "bidirectional"))
    )
    (net (code "65") (name "Net-(U$5-PadI3)") (class "Default")
      (node (ref "U$5") (pin "I3") (pinfunction "I3_I3") (pintype "bidirectional"))
      (node (ref "U$9") (pin "PD2") (pinfunction "PD2_PD2") (pintype "bidirectional"))
    )
    (net (code "66") (name "Net-(U$5-PadI4)") (class "Default")
      (node (ref "U$5") (pin "I4") (pinfunction "I4_I4") (pintype "bidirectional"))
      (node (ref "U$9") (pin "PD3") (pinfunction "PD3_PD3") (pintype "bidirectional"))
    )
    (net (code "67") (name "Net-(U$5-PadI5)") (class "Default")
      (node (ref "U$5") (pin "I5") (pinfunction "I5_I5") (pintype "bidirectional"))
      (node (ref "U$9") (pin "PD4") (pinfunction "PD4_PD4") (pintype "bidirectional"))
    )
    (net (code "68") (name "Net-(U$5-PadI6)") (class "Default")
      (node (ref "U$5") (pin "I6") (pinfunction "I6_I6") (pintype "bidirectional"))
      (node (ref "U$9") (pin "PD5") (pinfunction "PD5_PD5") (pintype "bidirectional"))
    )
    (net (code "69") (name "Net-(U$5-PadI7)") (class "Default")
      (node (ref "U$5") (pin "I7") (pinfunction "I7_I7") (pintype "bidirectional"))
      (node (ref "U$9") (pin "PD6") (pinfunction "PD6_PD6") (pintype "bidirectional"))
    )
    (net (code "70") (name "Net-(U$5-PadI8)") (class "Default")
      (node (ref "U$5") (pin "I8") (pinfunction "I8_I8") (pintype "bidirectional"))
      (node (ref "U$9") (pin "PD7") (pinfunction "PD7_PD7") (pintype "bidirectional"))
    )
    (net (code "71") (name "Net-(U$6-PadPA1)") (class "Default")
      (node (ref "U$6") (pin "PA1") (pinfunction "PA1_PA1") (pintype "bidirectional"))
      (node (ref "U$7") (pin "R7") (pinfunction "R7_R7") (pintype "bidirectional"))
    )
    (net (code "72") (name "Net-(U$6-PadPC0)") (class "Default")
      (node (ref "U$6") (pin "PC0") (pinfunction "PC0_PC0") (pintype "bidirectional"))
      (node (ref "U$7") (pin "R6") (pinfunction "R6_R6") (pintype "bidirectional"))
    )
    (net (code "73") (name "Net-(U$6-PadPC1)") (class "Default")
      (node (ref "U$6") (pin "PC1") (pinfunction "PC1_PC1") (pintype "bidirectional"))
      (node (ref "U$7") (pin "R5") (pinfunction "R5_R5") (pintype "bidirectional"))
    )
    (net (code "74") (name "Net-(U$6-PadPC2)") (class "Default")
      (node (ref "U$6") (pin "PC2") (pinfunction "PC2_PC2") (pintype "bidirectional"))
      (node (ref "U$7") (pin "R4") (pinfunction "R4_R4") (pintype "bidirectional"))
    )
    (net (code "75") (name "Net-(U$6-PadPC3)") (class "Default")
      (node (ref "U$6") (pin "PC3") (pinfunction "PC3_PC3") (pintype "bidirectional"))
      (node (ref "U$7") (pin "R3") (pinfunction "R3_R3") (pintype "bidirectional"))
    )
    (net (code "76") (name "Net-(U$6-PadPC4)") (class "Default")
      (node (ref "U$6") (pin "PC4") (pinfunction "PC4_PC4") (pintype "bidirectional"))
      (node (ref "U$7") (pin "R2") (pinfunction "R2_R2") (pintype "bidirectional"))
    )
    (net (code "77") (name "Net-(U$6-PadPC5)") (class "Default")
      (node (ref "U$6") (pin "PC5") (pinfunction "PC5_PC5") (pintype "bidirectional"))
      (node (ref "U$7") (pin "R1") (pinfunction "R1_R1") (pintype "bidirectional"))
    )
    (net (code "78") (name "Net-(U$6-PadPC7)") (class "Default")
      (node (ref "U$6") (pin "PC7") (pinfunction "PC7_PC7") (pintype "bidirectional"))
      (node (ref "U$7") (pin "R8") (pinfunction "R8_R8") (pintype "bidirectional"))
    )
    (net (code "79") (name "Net-(U$10-PadI1)") (class "Default")
      (node (ref "U$10") (pin "I1") (pinfunction "I1_I1") (pintype "bidirectional"))
      (node (ref "U$11") (pin "PD0") (pinfunction "PD0_PD0") (pintype "bidirectional"))
    )
    (net (code "80") (name "Net-(U$10-PadI2)") (class "Default")
      (node (ref "U$10") (pin "I2") (pinfunction "I2_I2") (pintype "bidirectional"))
      (node (ref "U$11") (pin "PD1") (pinfunction "PD1_PD1") (pintype "bidirectional"))
    )
    (net (code "81") (name "Net-(U$10-PadI3)") (class "Default")
      (node (ref "U$10") (pin "I3") (pinfunction "I3_I3") (pintype "bidirectional"))
      (node (ref "U$11") (pin "PD2") (pinfunction "PD2_PD2") (pintype "bidirectional"))
    )
    (net (code "82") (name "Net-(U$10-PadI4)") (class "Default")
      (node (ref "U$10") (pin "I4") (pinfunction "I4_I4") (pintype "bidirectional"))
      (node (ref "U$11") (pin "PD3") (pinfunction "PD3_PD3") (pintype "bidirectional"))
    )
    (net (code "83") (name "Net-(U$10-PadI5)") (class "Default")
      (node (ref "U$10") (pin "I5") (pinfunction "I5_I5") (pintype "bidirectional"))
      (node (ref "U$11") (pin "PD4") (pinfunction "PD4_PD4") (pintype "bidirectional"))
    )
    (net (code "84") (name "Net-(U$10-PadI6)") (class "Default")
      (node (ref "U$10") (pin "I6") (pinfunction "I6_I6") (pintype "bidirectional"))
      (node (ref "U$11") (pin "PD5") (pinfunction "PD5_PD5") (pintype "bidirectional"))
    )
    (net (code "85") (name "Net-(U$10-PadI7)") (class "Default")
      (node (ref "U$10") (pin "I7") (pinfunction "I7_I7") (pintype "bidirectional"))
      (node (ref "U$11") (pin "PD6") (pinfunction "PD6_PD6") (pintype "bidirectional"))
    )
    (net (code "86") (name "Net-(U$10-PadI8)") (class "Default")
      (node (ref "U$10") (pin "I8") (pinfunction "I8_I8") (pintype "bidirectional"))
      (node (ref "U$11") (pin "PD7") (pinfunction "PD7_PD7") (pintype "bidirectional"))
    )
    (net (code "87") (name "Net-(U$10-PadO1)") (class "Default")
      (node (ref "U$10") (pin "O1") (pinfunction "O1_O1") (pintype "bidirectional"))
      (node (ref "U$8") (pin "COL0") (pinfunction "COL0_COL0") (pintype "bidirectional"))
    )
    (net (code "88") (name "Net-(U$10-PadO2)") (class "Default")
      (node (ref "U$10") (pin "O2") (pinfunction "O2_O2") (pintype "bidirectional"))
      (node (ref "U$8") (pin "COL1") (pinfunction "COL1_COL1") (pintype "bidirectional"))
    )
    (net (code "89") (name "Net-(U$10-PadO3)") (class "Default")
      (node (ref "U$10") (pin "O3") (pinfunction "O3_O3") (pintype "bidirectional"))
      (node (ref "U$8") (pin "COL2") (pinfunction "COL2_COL2") (pintype "bidirectional"))
    )
    (net (code "90") (name "Net-(U$10-PadO4)") (class "Default")
      (node (ref "U$10") (pin "O4") (pinfunction "O4_O4") (pintype "bidirectional"))
      (node (ref "U$8") (pin "COL3") (pinfunction "COL3_COL3") (pintype "bidirectional"))
    )
    (net (code "91") (name "Net-(U$10-PadO5)") (class "Default")
      (node (ref "U$10") (pin "O5") (pinfunction "O5_O5") (pintype "bidirectional"))
      (node (ref "U$8") (pin "COL4") (pinfunction "COL4_COL4") (pintype "bidirectional"))
    )
    (net (code "92") (name "Net-(U$10-PadO6)") (class "Default")
      (node (ref "U$10") (pin "O6") (pinfunction "O6_O6") (pintype "bidirectional"))
      (node (ref "U$8") (pin "COL5") (pinfunction "COL5_COL5") (pintype "bidirectional"))
    )
    (net (code "93") (name "Net-(U$10-PadO7)") (class "Default")
      (node (ref "U$10") (pin "O7") (pinfunction "O7_O7") (pintype "bidirectional"))
      (node (ref "U$8") (pin "COL6") (pinfunction "COL6_COL6") (pintype "bidirectional"))
    )
    (net (code "94") (name "Net-(U$10-PadO8)") (class "Default")
      (node (ref "U$10") (pin "O8") (pinfunction "O8_O8") (pintype "bidirectional"))
      (node (ref "U$8") (pin "COL7") (pinfunction "COL7_COL7") (pintype "bidirectional"))
    )
    (net (code "95") (name "Net-(U$11-PadPA1)") (class "Default")
      (node (ref "U$11") (pin "PA1") (pinfunction "PA1_PA1") (pintype "bidirectional"))
      (node (ref "U$12") (pin "R7") (pinfunction "R7_R7") (pintype "bidirectional"))
    )
    (net (code "96") (name "Net-(U$11-PadPC0)") (class "Default")
      (node (ref "U$11") (pin "PC0") (pinfunction "PC0_PC0") (pintype "bidirectional"))
      (node (ref "U$12") (pin "R6") (pinfunction "R6_R6") (pintype "bidirectional"))
    )
    (net (code "97") (name "Net-(U$11-PadPC1)") (class "Default")
      (node (ref "U$11") (pin "PC1") (pinfunction "PC1_PC1") (pintype "bidirectional"))
      (node (ref "U$12") (pin "R5") (pinfunction "R5_R5") (pintype "bidirectional"))
    )
    (net (code "98") (name "Net-(U$11-PadPC2)") (class "Default")
      (node (ref "U$11") (pin "PC2") (pinfunction "PC2_PC2") (pintype "bidirectional"))
      (node (ref "U$12") (pin "R4") (pinfunction "R4_R4") (pintype "bidirectional"))
    )
    (net (code "99") (name "Net-(U$11-PadPC3)") (class "Default")
      (node (ref "U$11") (pin "PC3") (pinfunction "PC3_PC3") (pintype "bidirectional"))
      (node (ref "U$12") (pin "R3") (pinfunction "R3_R3") (pintype "bidirectional"))
    )
    (net (code "100") (name "Net-(U$11-PadPC4)") (class "Default")
      (node (ref "U$11") (pin "PC4") (pinfunction "PC4_PC4") (pintype "bidirectional"))
      (node (ref "U$12") (pin "R2") (pinfunction "R2_R2") (pintype "bidirectional"))
    )
    (net (code "101") (name "Net-(U$11-PadPC5)") (class "Default")
      (node (ref "U$11") (pin "PC5") (pinfunction "PC5_PC5") (pintype "bidirectional"))
      (node (ref "U$12") (pin "R1") (pinfunction "R1_R1") (pintype "bidirectional"))
    )
    (net (code "102") (name "Net-(U$11-PadPC7)") (class "Default")
      (node (ref "U$11") (pin "PC7") (pinfunction "PC7_PC7") (pintype "bidirectional"))
      (node (ref "U$12") (pin "R8") (pinfunction "R8_R8") (pintype "bidirectional"))
    )
    (net (code "103") (name "Net-(U$12-Pad1R)") (class "Default")
      (node (ref "U$12") (pin "1R") (pinfunction "1R_1R") (pintype "bidirectional"))
      (node (ref "U$8") (pin "ROW7") (pinfunction "ROW7_ROW7") (pintype "bidirectional"))
    )
    (net (code "104") (name "Net-(U$12-Pad2R)") (class "Default")
      (node (ref "U$12") (pin "2R") (pinfunction "2R_2R") (pintype "bidirectional"))
      (node (ref "U$8") (pin "ROW6") (pinfunction "ROW6_ROW6") (pintype "bidirectional"))
    )
    (net (code "105") (name "Net-(U$12-Pad3R)") (class "Default")
      (node (ref "U$12") (pin "3R") (pinfunction "3R_3R") (pintype "bidirectional"))
      (node (ref "U$8") (pin "ROW5") (pinfunction "ROW5_ROW5") (pintype "bidirectional"))
    )
    (net (code "106") (name "Net-(U$12-Pad4R)") (class "Default")
      (node (ref "U$12") (pin "4R") (pinfunction "4R_4R") (pintype "bidirectional"))
      (node (ref "U$8") (pin "ROW4") (pinfunction "ROW4_ROW4") (pintype "bidirectional"))
    )
    (net (code "107") (name "Net-(U$12-Pad5R)") (class "Default")
      (node (ref "U$12") (pin "5R") (pinfunction "5R_5R") (pintype "bidirectional"))
      (node (ref "U$8") (pin "ROW3") (pinfunction "ROW3_ROW3") (pintype "bidirectional"))
    )
    (net (code "108") (name "Net-(U$12-Pad6R)") (class "Default")
      (node (ref "U$12") (pin "6R") (pinfunction "6R_6R") (pintype "bidirectional"))
      (node (ref "U$8") (pin "ROW2") (pinfunction "ROW2_ROW2") (pintype "bidirectional"))
    )
    (net (code "109") (name "Net-(U$12-Pad7R)") (class "Default")
      (node (ref "U$12") (pin "7R") (pinfunction "7R_7R") (pintype "bidirectional"))
      (node (ref "U$8") (pin "ROW1") (pinfunction "ROW1_ROW1") (pintype "bidirectional"))
    )
    (net (code "110") (name "Net-(U$12-Pad8R)") (class "Default")
      (node (ref "U$12") (pin "8R") (pinfunction "8R_8R") (pintype "bidirectional"))
      (node (ref "U$8") (pin "ROW0") (pinfunction "ROW0_ROW0") (pintype "bidirectional"))
    )
    (net (code "111") (name "Net-(U$13-PadCOL0)") (class "Default")
      (node (ref "U$13") (pin "COL0") (pinfunction "COL0_COL0") (pintype "bidirectional"))
      (node (ref "U$14") (pin "O1") (pinfunction "O1_O1") (pintype "bidirectional"))
    )
    (net (code "112") (name "Net-(U$13-PadCOL1)") (class "Default")
      (node (ref "U$13") (pin "COL1") (pinfunction "COL1_COL1") (pintype "bidirectional"))
      (node (ref "U$14") (pin "O2") (pinfunction "O2_O2") (pintype "bidirectional"))
    )
    (net (code "113") (name "Net-(U$13-PadCOL2)") (class "Default")
      (node (ref "U$13") (pin "COL2") (pinfunction "COL2_COL2") (pintype "bidirectional"))
      (node (ref "U$14") (pin "O3") (pinfunction "O3_O3") (pintype "bidirectional"))
    )
    (net (code "114") (name "Net-(U$13-PadCOL3)") (class "Default")
      (node (ref "U$13") (pin "COL3") (pinfunction "COL3_COL3") (pintype "bidirectional"))
      (node (ref "U$14") (pin "O4") (pinfunction "O4_O4") (pintype "bidirectional"))
    )
    (net (code "115") (name "Net-(U$13-PadCOL4)") (class "Default")
      (node (ref "U$13") (pin "COL4") (pinfunction "COL4_COL4") (pintype "bidirectional"))
      (node (ref "U$14") (pin "O5") (pinfunction "O5_O5") (pintype "bidirectional"))
    )
    (net (code "116") (name "Net-(U$13-PadCOL5)") (class "Default")
      (node (ref "U$13") (pin "COL5") (pinfunction "COL5_COL5") (pintype "bidirectional"))
      (node (ref "U$14") (pin "O6") (pinfunction "O6_O6") (pintype "bidirectional"))
    )
    (net (code "117") (name "Net-(U$13-PadCOL6)") (class "Default")
      (node (ref "U$13") (pin "COL6") (pinfunction "COL6_COL6") (pintype "bidirectional"))
      (node (ref "U$14") (pin "O7") (pinfunction "O7_O7") (pintype "bidirectional"))
    )
    (net (code "118") (name "Net-(U$13-PadCOL7)") (class "Default")
      (node (ref "U$13") (pin "COL7") (pinfunction "COL7_COL7") (pintype "bidirectional"))
      (node (ref "U$14") (pin "O8") (pinfunction "O8_O8") (pintype "bidirectional"))
    )
    (net (code "119") (name "Net-(U$13-PadROW0)") (class "Default")
      (node (ref "U$13") (pin "ROW0") (pinfunction "ROW0_ROW0") (pintype "bidirectional"))
      (node (ref "U$16") (pin "8R") (pinfunction "8R_8R") (pintype "bidirectional"))
    )
    (net (code "120") (name "Net-(U$13-PadROW1)") (class "Default")
      (node (ref "U$13") (pin "ROW1") (pinfunction "ROW1_ROW1") (pintype "bidirectional"))
      (node (ref "U$16") (pin "7R") (pinfunction "7R_7R") (pintype "bidirectional"))
    )
    (net (code "121") (name "Net-(U$13-PadROW2)") (class "Default")
      (node (ref "U$13") (pin "ROW2") (pinfunction "ROW2_ROW2") (pintype "bidirectional"))
      (node (ref "U$16") (pin "6R") (pinfunction "6R_6R") (pintype "bidirectional"))
    )
    (net (code "122") (name "Net-(U$13-PadROW3)") (class "Default")
      (node (ref "U$13") (pin "ROW3") (pinfunction "ROW3_ROW3") (pintype "bidirectional"))
      (node (ref "U$16") (pin "5R") (pinfunction "5R_5R") (pintype "bidirectional"))
    )
    (net (code "123") (name "Net-(U$13-PadROW4)") (class "Default")
      (node (ref "U$13") (pin "ROW4") (pinfunction "ROW4_ROW4") (pintype "bidirectional"))
      (node (ref "U$16") (pin "4R") (pinfunction "4R_4R") (pintype "bidirectional"))
    )
    (net (code "124") (name "Net-(U$13-PadROW5)") (class "Default")
      (node (ref "U$13") (pin "ROW5") (pinfunction "ROW5_ROW5") (pintype "bidirectional"))
      (node (ref "U$16") (pin "3R") (pinfunction "3R_3R") (pintype "bidirectional"))
    )
    (net (code "125") (name "Net-(U$13-PadROW6)") (class "Default")
      (node (ref "U$13") (pin "ROW6") (pinfunction "ROW6_ROW6") (pintype "bidirectional"))
      (node (ref "U$16") (pin "2R") (pinfunction "2R_2R") (pintype "bidirectional"))
    )
    (net (code "126") (name "Net-(U$13-PadROW7)") (class "Default")
      (node (ref "U$13") (pin "ROW7") (pinfunction "ROW7_ROW7") (pintype "bidirectional"))
      (node (ref "U$16") (pin "1R") (pinfunction "1R_1R") (pintype "bidirectional"))
    )
    (net (code "127") (name "Net-(U$14-PadI1)") (class "Default")
      (node (ref "U$14") (pin "I1") (pinfunction "I1_I1") (pintype "bidirectional"))
      (node (ref "U$15") (pin "PD0") (pinfunction "PD0_PD0") (pintype "bidirectional"))
    )
    (net (code "128") (name "Net-(U$14-PadI2)") (class "Default")
      (node (ref "U$14") (pin "I2") (pinfunction "I2_I2") (pintype "bidirectional"))
      (node (ref "U$15") (pin "PD1") (pinfunction "PD1_PD1") (pintype "bidirectional"))
    )
    (net (code "129") (name "Net-(U$14-PadI3)") (class "Default")
      (node (ref "U$14") (pin "I3") (pinfunction "I3_I3") (pintype "bidirectional"))
      (node (ref "U$15") (pin "PD2") (pinfunction "PD2_PD2") (pintype "bidirectional"))
    )
    (net (code "130") (name "Net-(U$14-PadI4)") (class "Default")
      (node (ref "U$14") (pin "I4") (pinfunction "I4_I4") (pintype "bidirectional"))
      (node (ref "U$15") (pin "PD3") (pinfunction "PD3_PD3") (pintype "bidirectional"))
    )
    (net (code "131") (name "Net-(U$14-PadI5)") (class "Default")
      (node (ref "U$14") (pin "I5") (pinfunction "I5_I5") (pintype "bidirectional"))
      (node (ref "U$15") (pin "PD4") (pinfunction "PD4_PD4") (pintype "bidirectional"))
    )
    (net (code "132") (name "Net-(U$14-PadI6)") (class "Default")
      (node (ref "U$14") (pin "I6") (pinfunction "I6_I6") (pintype "bidirectional"))
      (node (ref "U$15") (pin "PD5") (pinfunction "PD5_PD5") (pintype "bidirectional"))
    )
    (net (code "133") (name "Net-(U$14-PadI7)") (class "Default")
      (node (ref "U$14") (pin "I7") (pinfunction "I7_I7") (pintype "bidirectional"))
      (node (ref "U$15") (pin "PD6") (pinfunction "PD6_PD6") (pintype "bidirectional"))
    )
    (net (code "134") (name "Net-(U$14-PadI8)") (class "Default")
      (node (ref "U$14") (pin "I8") (pinfunction "I8_I8") (pintype "bidirectional"))
      (node (ref "U$15") (pin "PD7") (pinfunction "PD7_PD7") (pintype "bidirectional"))
    )
    (net (code "135") (name "Net-(U$15-PadPA1)") (class "Default")
      (node (ref "U$15") (pin "PA1") (pinfunction "PA1_PA1") (pintype "bidirectional"))
      (node (ref "U$16") (pin "R7") (pinfunction "R7_R7") (pintype "bidirectional"))
    )
    (net (code "136") (name "Net-(U$15-PadPC0)") (class "Default")
      (node (ref "U$15") (pin "PC0") (pinfunction "PC0_PC0") (pintype "bidirectional"))
      (node (ref "U$16") (pin "R6") (pinfunction "R6_R6") (pintype "bidirectional"))
    )
    (net (code "137") (name "Net-(U$15-PadPC1)") (class "Default")
      (node (ref "U$15") (pin "PC1") (pinfunction "PC1_PC1") (pintype "bidirectional"))
      (node (ref "U$16") (pin "R5") (pinfunction "R5_R5") (pintype "bidirectional"))
    )
    (net (code "138") (name "Net-(U$15-PadPC2)") (class "Default")
      (node (ref "U$15") (pin "PC2") (pinfunction "PC2_PC2") (pintype "bidirectional"))
      (node (ref "U$16") (pin "R4") (pinfunction "R4_R4") (pintype "bidirectional"))
    )
    (net (code "139") (name "Net-(U$15-PadPC3)") (class "Default")
      (node (ref "U$15") (pin "PC3") (pinfunction "PC3_PC3") (pintype "bidirectional"))
      (node (ref "U$16") (pin "R3") (pinfunction "R3_R3") (pintype "bidirectional"))
    )
    (net (code "140") (name "Net-(U$15-PadPC4)") (class "Default")
      (node (ref "U$15") (pin "PC4") (pinfunction "PC4_PC4") (pintype "bidirectional"))
      (node (ref "U$16") (pin "R2") (pinfunction "R2_R2") (pintype "bidirectional"))
    )
    (net (code "141") (name "Net-(U$15-PadPC5)") (class "Default")
      (node (ref "U$15") (pin "PC5") (pinfunction "PC5_PC5") (pintype "bidirectional"))
      (node (ref "U$16") (pin "R1") (pinfunction "R1_R1") (pintype "bidirectional"))
    )
    (net (code "142") (name "Net-(U$15-PadPC7)") (class "Default")
      (node (ref "U$15") (pin "PC7") (pinfunction "PC7_PC7") (pintype "bidirectional"))
      (node (ref "U$16") (pin "R8") (pinfunction "R8_R8") (pintype "bidirectional"))
    )
    (net (code "143") (name "Net-(U$23-BYP)") (class "Default")
      (node (ref "C3") (pin "1") (pinfunction "1_1") (pintype "passive"))
      (node (ref "U$23") (pin "4") (pinfunction "BYP_4") (pintype "bidirectional"))
    )
    (net (code "144") (name "Net-(U$25-BYPASS)") (class "Default")
      (node (ref "C7") (pin "1") (pinfunction "1_1") (pintype "passive"))
      (node (ref "U$25") (pin "7") (pinfunction "BYPASS_7") (pintype "bidirectional"))
    )
    (net (code "145") (name "Net-(U$25-VOUT)") (class "Default")
      (node (ref "C5") (pin "+") (pinfunction "+_+") (pintype "passive"))
      (node (ref "C6") (pin "1") (pinfunction "1_1") (pintype "passive"))
      (node (ref "U$25") (pin "5") (pinfunction "VOUT_5") (pintype "bidirectional"))
    )
    (net (code "146") (name "RESET") (class "Default")
      (node (ref "J1") (pin "5") (pinfunction "5_5") (pintype "passive"))
      (node (ref "J2") (pin "5") (pinfunction "5_5") (pintype "passive"))
      (node (ref "J3") (pin "5") (pinfunction "5_5") (pintype "passive"))
      (node (ref "J4") (pin "5") (pinfunction "5_5") (pintype "passive"))
      (node (ref "R5") (pin "1") (pinfunction "1_1") (pintype "passive"))
      (node (ref "R6") (pin "1") (pinfunction "1_1") (pintype "passive"))
      (node (ref "R8") (pin "1") (pinfunction "1_1") (pintype "passive"))
      (node (ref "R9") (pin "1") (pinfunction "1_1") (pintype "passive"))
      (node (ref "U$11") (pin "PC6") (pinfunction "PC6_PC6") (pintype "bidirectional"))
      (node (ref "U$15") (pin "PC6") (pinfunction "PC6_PC6") (pintype "bidirectional"))
      (node (ref "U$6") (pin "PC6") (pinfunction "PC6_PC6") (pintype "bidirectional"))
      (node (ref "U$9") (pin "PC6") (pinfunction "PC6_PC6") (pintype "bidirectional"))
    )
    (net (code "147") (name "RIGHT") (class "Default")
      (node (ref "PI-HEADER") (pin "12") (pinfunction "12_12") (pintype "passive"))
      (node (ref "U$19") (pin "2") (pinfunction "2_2") (pintype "bidirectional"))
    )
    (net (code "148") (name "SCK") (class "Default")
      (node (ref "J1") (pin "3") (pinfunction "3_3") (pintype "passive"))
      (node (ref "J2") (pin "3") (pinfunction "3_3") (pintype "passive"))
      (node (ref "J3") (pin "3") (pinfunction "3_3") (pintype "passive"))
      (node (ref "J4") (pin "3") (pinfunction "3_3") (pintype "passive"))
      (node (ref "PI-HEADER") (pin "23") (pinfunction "23_23") (pintype "passive"))
      (node (ref "U$11") (pin "PB5") (pinfunction "PB5_PB5") (pintype "bidirectional"))
      (node (ref "U$15") (pin "PB5") (pinfunction "PB5_PB5") (pintype "bidirectional"))
      (node (ref "U$6") (pin "PB5") (pinfunction "PB5_PB5") (pintype "bidirectional"))
      (node (ref "U$9") (pin "PB5") (pinfunction "PB5_PB5") (pintype "bidirectional"))
    )
    (net (code "149") (name "SCL") (class "Default")
      (node (ref "PI-HEADER") (pin "5") (pinfunction "5_5") (pintype "passive"))
      (node (ref "R2") (pin "2") (pinfunction "2_2") (pintype "passive"))
      (node (ref "U$23") (pin "2") (pinfunction "SCL_2") (pintype "bidirectional"))
    )
    (net (code "150") (name "SDA") (class "Default")
      (node (ref "PI-HEADER") (pin "3") (pinfunction "3_3") (pintype "passive"))
      (node (ref "R1") (pin "1") (pinfunction "1_1") (pintype "passive"))
      (node (ref "U$23") (pin "10") (pinfunction "SDA_10") (pintype "bidirectional"))
    )
    (net (code "151") (name "SELECT") (class "Default")
      (node (ref "PI-HEADER") (pin "15") (pinfunction "15_15") (pintype "passive"))
      (node (ref "U$26") (pin "1") (pinfunction "P$1_1") (pintype "bidirectional"))
    )
    (net (code "152") (name "SPK") (class "Default")
      (node (ref "C5") (pin "-") (pinfunction "-_-") (pintype "passive"))
      (node (ref "U$29") (pin "1") (pinfunction "1_1") (pintype "bidirectional"))
    )
    (net (code "153") (name "SS") (class "Default")
      (node (ref "PI-HEADER") (pin "24") (pinfunction "24_24") (pintype "passive"))
      (node (ref "U$11") (pin "PB2") (pinfunction "PB2_PB2") (pintype "bidirectional"))
      (node (ref "U$15") (pin "PB2") (pinfunction "PB2_PB2") (pintype "bidirectional"))
      (node (ref "U$6") (pin "PB2") (pinfunction "PB2_PB2") (pintype "bidirectional"))
      (node (ref "U$9") (pin "PB2") (pinfunction "PB2_PB2") (pintype "bidirectional"))
    )
    (net (code "154") (name "START") (class "Default")
      (node (ref "PI-HEADER") (pin "13") (pinfunction "13_13") (pintype "passive"))
      (node (ref "U$24") (pin "1") (pinfunction "P$1_1") (pintype "bidirectional"))
    )
    (net (code "155") (name "UP") (class "Default")
      (node (ref "PI-HEADER") (pin "22") (pinfunction "22_22") (pintype "passive"))
      (node (ref "U$17") (pin "2") (pinfunction "2_2") (pintype "bidirectional"))
    )
    (net (code "156") (name "VCC") (class "Default")
      (node (ref "C1") (pin "1") (pinfunction "1_1") (pintype "passive"))
      (node (ref "C10") (pin "1") (pinfunction "1_1") (pintype "passive"))
      (node (ref "C11") (pin "1") (pinfunction "1_1") (pintype "passive"))
      (node (ref "C2") (pin "1") (pinfunction "1_1") (pintype "passive"))
      (node (ref "C4") (pin "1") (pinfunction "1_1") (pintype "passive"))
      (node (ref "C8") (pin "1") (pinfunction "1_1") (pintype "passive"))
      (node (ref "C9") (pin "1") (pinfunction "1_1") (pintype "passive"))
      (node (ref "J1") (pin "2") (pinfunction "2_2") (pintype "passive"))
      (node (ref "J2") (pin "2") (pinfunction "2_2") (pintype "passive"))
      (node (ref "J3") (pin "2") (pinfunction "2_2") (pintype "passive"))
      (node (ref "J4") (pin "2") (pinfunction "2_2") (pintype "passive"))
      (node (ref "R1") (pin "2") (pinfunction "2_2") (pintype "passive"))
      (node (ref "R2") (pin "1") (pinfunction "1_1") (pintype "passive"))
      (node (ref "R5") (pin "2") (pinfunction "2_2") (pintype "passive"))
      (node (ref "R6") (pin "2") (pinfunction "2_2") (pintype "passive"))
      (node (ref "R8") (pin "2") (pinfunction "2_2") (pintype "passive"))
      (node (ref "R9") (pin "2") (pinfunction "2_2") (pintype "passive"))
      (node (ref "U$10") (pin "COMMON") (pinfunction "COMMON_COMMON") (pintype "bidirectional"))
      (node (ref "U$11") (pin "AVCC") (pinfunction "AVCC_AVCC") (pintype "bidirectional"))
      (node (ref "U$11") (pin "VCC") (pinfunction "VCC_VCC") (pintype "bidirectional"))
      (node (ref "U$14") (pin "COMMON") (pinfunction "COMMON_COMMON") (pintype "bidirectional"))
      (node (ref "U$15") (pin "AVCC") (pinfunction "AVCC_AVCC") (pintype "bidirectional"))
      (node (ref "U$15") (pin "VCC") (pinfunction "VCC_VCC") (pintype "bidirectional"))
      (node (ref "U$23") (pin "1") (pinfunction "VDD_1") (pintype "bidirectional"))
      (node (ref "U$23") (pin "8") (pinfunction "VDDIO_8") (pintype "bidirectional"))
      (node (ref "U$25") (pin "6") (pinfunction "VS_6") (pintype "bidirectional"))
      (node (ref "U$30") (pin "4") (pinfunction "4_4") (pintype "bidirectional"))
      (node (ref "U$4") (pin "COMMON") (pinfunction "COMMON_COMMON") (pintype "bidirectional"))
      (node (ref "U$5") (pin "COMMON") (pinfunction "COMMON_COMMON") (pintype "bidirectional"))
      (node (ref "U$6") (pin "AVCC") (pinfunction "AVCC_AVCC") (pintype "bidirectional"))
      (node (ref "U$6") (pin "VCC") (pinfunction "VCC_VCC") (pintype "bidirectional"))
      (node (ref "U$9") (pin "AVCC") (pinfunction "AVCC_AVCC") (pintype "bidirectional"))
      (node (ref "U$9") (pin "VCC") (pinfunction "VCC_VCC") (pintype "bidirectional"))
    )
    (net (code "157") (name "unconnected-(PI-HEADER-Pad1)") (class "Default")
      (node (ref "PI-HEADER") (pin "1") (pinfunction "1_1") (pintype "passive"))
    )
    (net (code "158") (name "unconnected-(PI-HEADER-Pad2)") (class "Default")
      (node (ref "PI-HEADER") (pin "2") (pinfunction "2_2") (pintype "passive"))
    )
    (net (code "159") (name "unconnected-(PI-HEADER-Pad4)") (class "Default")
      (node (ref "PI-HEADER") (pin "4") (pinfunction "4_4") (pintype "passive"))
    )
    (net (code "160") (name "unconnected-(PI-HEADER-Pad9)") (class "Default")
      (node (ref "PI-HEADER") (pin "9") (pinfunction "9_9") (pintype "passive"))
    )
    (net (code "161") (name "unconnected-(PI-HEADER-Pad14)") (class "Default")
      (node (ref "PI-HEADER") (pin "14") (pinfunction "14_14") (pintype "passive"))
    )
    (net (code "162") (name "unconnected-(PI-HEADER-Pad17)") (class "Default")
      (node (ref "PI-HEADER") (pin "17") (pinfunction "17_17") (pintype "passive"))
    )
    (net (code "163") (name "unconnected-(PI-HEADER-Pad20)") (class "Default")
      (node (ref "PI-HEADER") (pin "20") (pinfunction "20_20") (pintype "passive"))
    )
    (net (code "164") (name "unconnected-(PI-HEADER-Pad25)") (class "Default")
      (node (ref "PI-HEADER") (pin "25") (pinfunction "25_25") (pintype "passive"))
    )
    (net (code "165") (name "unconnected-(PI-HEADER-Pad26)") (class "Default")
      (node (ref "PI-HEADER") (pin "26") (pinfunction "26_26") (pintype "passive"))
    )
    (net (code "166") (name "unconnected-(U$6-PadPA0)") (class "Default")
      (node (ref "U$6") (pin "PA0") (pinfunction "PA0_PA0") (pintype "bidirectional"))
    )
    (net (code "167") (name "unconnected-(U$6-PadPA2)") (class "Default")
      (node (ref "U$6") (pin "PA2") (pinfunction "PA2_PA2") (pintype "bidirectional"))
    )
    (net (code "168") (name "unconnected-(U$6-PadPA3)") (class "Default")
      (node (ref "U$6") (pin "PA3") (pinfunction "PA3_PA3") (pintype "bidirectional"))
    )
    (net (code "169") (name "unconnected-(U$6-PadPB0)") (class "Default")
      (node (ref "U$6") (pin "PB0") (pinfunction "PB0_PB0") (pintype "bidirectional"))
    )
    (net (code "170") (name "unconnected-(U$6-PadPB1)") (class "Default")
      (node (ref "U$6") (pin "PB1") (pinfunction "PB1_PB1") (pintype "bidirectional"))
    )
    (net (code "171") (name "unconnected-(U$6-PadPB6)") (class "Default")
      (node (ref "U$6") (pin "PB6") (pinfunction "PB6_PB6") (pintype "bidirectional"))
    )
    (net (code "172") (name "unconnected-(U$6-PadPB7)") (class "Default")
      (node (ref "U$6") (pin "PB7") (pinfunction "PB7_PB7") (pintype "bidirectional"))
    )
    (net (code "173") (name "unconnected-(U$9-PadPA0)") (class "Default")
      (node (ref "U$9") (pin "PA0") (pinfunction "PA0_PA0") (pintype "bidirectional"))
    )
    (net (code "174") (name "unconnected-(U$9-PadPA2)") (class "Default")
      (node (ref "U$9") (pin "PA2") (pinfunction "PA2_PA2") (pintype "bidirectional"))
    )
    (net (code "175") (name "unconnected-(U$9-PadPA3)") (class "Default")
      (node (ref "U$9") (pin "PA3") (pinfunction "PA3_PA3") (pintype "bidirectional"))
    )
    (net (code "176") (name "unconnected-(U$9-PadPB0)") (class "Default")
      (node (ref "U$9") (pin "PB0") (pinfunction "PB0_PB0") (pintype "bidirectional"))
    )
    (net (code "177") (name "unconnected-(U$9-PadPB1)") (class "Default")
      (node (ref "U$9") (pin "PB1") (pinfunction "PB1_PB1") (pintype "bidirectional"))
    )
    (net (code "178") (name "unconnected-(U$9-PadPB6)") (class "Default")
      (node (ref "U$9") (pin "PB6") (pinfunction "PB6_PB6") (pintype "bidirectional"))
    )
    (net (code "179") (name "unconnected-(U$9-PadPB7)") (class "Default")
      (node (ref "U$9") (pin "PB7") (pinfunction "PB7_PB7") (pintype "bidirectional"))
    )
    (net (code "180") (name "unconnected-(U$11-PadPA0)") (class "Default")
      (node (ref "U$11") (pin "PA0") (pinfunction "PA0_PA0") (pintype "bidirectional"))
    )
    (net (code "181") (name "unconnected-(U$11-PadPA2)") (class "Default")
      (node (ref "U$11") (pin "PA2") (pinfunction "PA2_PA2") (pintype "bidirectional"))
    )
    (net (code "182") (name "unconnected-(U$11-PadPA3)") (class "Default")
      (node (ref "U$11") (pin "PA3") (pinfunction "PA3_PA3") (pintype "bidirectional"))
    )
    (net (code "183") (name "unconnected-(U$11-PadPB0)") (class "Default")
      (node (ref "U$11") (pin "PB0") (pinfunction "PB0_PB0") (pintype "bidirectional"))
    )
    (net (code "184") (name "unconnected-(U$11-PadPB1)") (class "Default")
      (node (ref "U$11") (pin "PB1") (pinfunction "PB1_PB1") (pintype "bidirectional"))
    )
    (net (code "185") (name "unconnected-(U$11-PadPB6)") (class "Default")
      (node (ref "U$11") (pin "PB6") (pinfunction "PB6_PB6") (pintype "bidirectional"))
    )
    (net (code "186") (name "unconnected-(U$11-PadPB7)") (class "Default")
      (node (ref "U$11") (pin "PB7") (pinfunction "PB7_PB7") (pintype "bidirectional"))
    )
    (net (code "187") (name "unconnected-(U$15-PadPA0)") (class "Default")
      (node (ref "U$15") (pin "PA0") (pinfunction "PA0_PA0") (pintype "bidirectional"))
    )
    (net (code "188") (name "unconnected-(U$15-PadPA2)") (class "Default")
      (node (ref "U$15") (pin "PA2") (pinfunction "PA2_PA2") (pintype "bidirectional"))
    )
    (net (code "189") (name "unconnected-(U$15-PadPA3)") (class "Default")
      (node (ref "U$15") (pin "PA3") (pinfunction "PA3_PA3") (pintype "bidirectional"))
    )
    (net (code "190") (name "unconnected-(U$15-PadPB0)") (class "Default")
      (node (ref "U$15") (pin "PB0") (pinfunction "PB0_PB0") (pintype "bidirectional"))
    )
    (net (code "191") (name "unconnected-(U$15-PadPB1)") (class "Default")
      (node (ref "U$15") (pin "PB1") (pinfunction "PB1_PB1") (pintype "bidirectional"))
    )
    (net (code "192") (name "unconnected-(U$15-PadPB6)") (class "Default")
      (node (ref "U$15") (pin "PB6") (pinfunction "PB6_PB6") (pintype "bidirectional"))
    )
    (net (code "193") (name "unconnected-(U$15-PadPB7)") (class "Default")
      (node (ref "U$15") (pin "PB7") (pinfunction "PB7_PB7") (pintype "bidirectional"))
    )
    (net (code "194") (name "unconnected-(U$17-Pad1)") (class "Default")
      (node (ref "U$17") (pin "1") (pinfunction "1_1") (pintype "bidirectional"))
    )
    (net (code "195") (name "unconnected-(U$17-Pad3)") (class "Default")
      (node (ref "U$17") (pin "3") (pinfunction "3_3") (pintype "bidirectional"))
    )
    (net (code "196") (name "unconnected-(U$18-Pad1)") (class "Default")
      (node (ref "U$18") (pin "1") (pinfunction "1_1") (pintype "bidirectional"))
    )
    (net (code "197") (name "unconnected-(U$18-Pad3)") (class "Default")
      (node (ref "U$18") (pin "3") (pinfunction "3_3") (pintype "bidirectional"))
    )
    (net (code "198") (name "unconnected-(U$19-Pad1)") (class "Default")
      (node (ref "U$19") (pin "1") (pinfunction "1_1") (pintype "bidirectional"))
    )
    (net (code "199") (name "unconnected-(U$19-Pad3)") (class "Default")
      (node (ref "U$19") (pin "3") (pinfunction "3_3") (pintype "bidirectional"))
    )
    (net (code "200") (name "unconnected-(U$20-Pad1)") (class "Default")
      (node (ref "U$20") (pin "1") (pinfunction "1_1") (pintype "bidirectional"))
    )
    (net (code "201") (name "unconnected-(U$20-Pad3)") (class "Default")
      (node (ref "U$20") (pin "3") (pinfunction "3_3") (pintype "bidirectional"))
    )
    (net (code "202") (name "unconnected-(U$21-Pad2)") (class "Default")
      (node (ref "U$21") (pin "2") (pinfunction "2_2") (pintype "bidirectional"))
    )
    (net (code "203") (name "unconnected-(U$21-Pad4)") (class "Default")
      (node (ref "U$21") (pin "4") (pinfunction "4_4") (pintype "bidirectional"))
    )
    (net (code "204") (name "unconnected-(U$22-Pad2)") (class "Default")
      (node (ref "U$22") (pin "2") (pinfunction "2_2") (pintype "bidirectional"))
    )
    (net (code "205") (name "unconnected-(U$22-Pad4)") (class "Default")
      (node (ref "U$22") (pin "4") (pinfunction "4_4") (pintype "bidirectional"))
    )
    (net (code "206") (name "unconnected-(U$24-P$2-Pad2)") (class "Default")
      (node (ref "U$24") (pin "2") (pinfunction "P$2_2") (pintype "bidirectional"))
    )
    (net (code "207") (name "unconnected-(U$24-P$3-Pad3)") (class "Default")
      (node (ref "U$24") (pin "3") (pinfunction "P$3_3") (pintype "bidirectional"))
    )
    (net (code "208") (name "unconnected-(U$25-GAIN1-Pad1)") (class "Default")
      (node (ref "U$25") (pin "1") (pinfunction "GAIN1_1") (pintype "bidirectional"))
    )
    (net (code "209") (name "unconnected-(U$25-GAIN2-Pad8)") (class "Default")
      (node (ref "U$25") (pin "8") (pinfunction "GAIN2_8") (pintype "bidirectional"))
    )
    (net (code "210") (name "unconnected-(U$26-P$2-Pad2)") (class "Default")
      (node (ref "U$26") (pin "2") (pinfunction "P$2_2") (pintype "bidirectional"))
    )
    (net (code "211") (name "unconnected-(U$26-P$3-Pad3)") (class "Default")
      (node (ref "U$26") (pin "3") (pinfunction "P$3_3") (pintype "bidirectional"))
    )
    (net (code "212") (name "unconnected-(U$30-Pad3)") (class "Default")
      (node (ref "U$30") (pin "3") (pinfunction "3_3") (pintype "bidirectional"))
    )
  )
)
